# RT_SUPER_C.net
KiCad netlist of a schematic drawn in Altium Designer
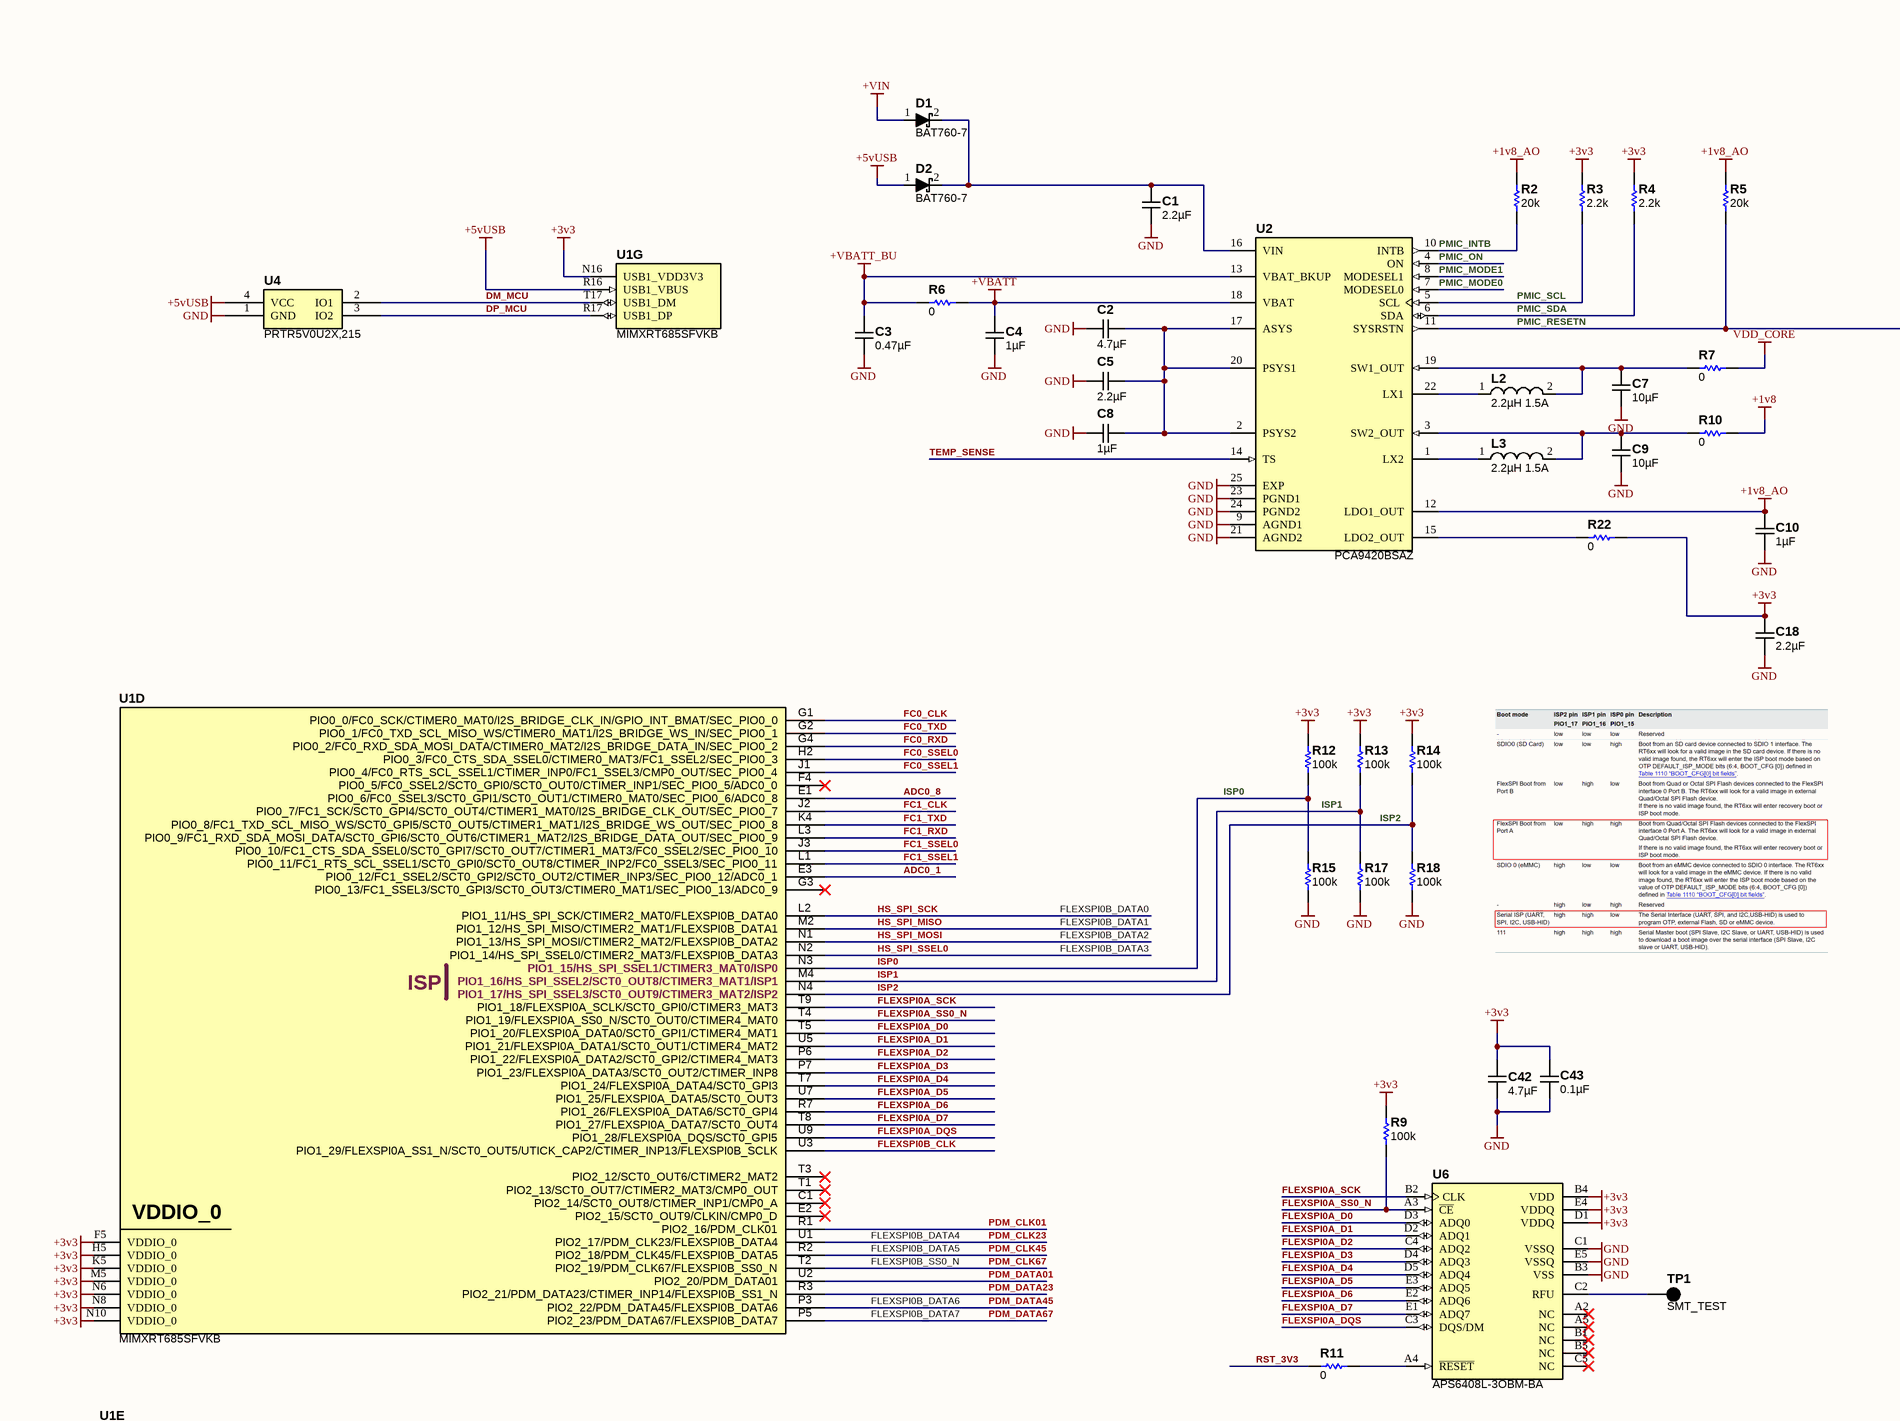
[diagram p0: RT_SUPER_C.SchDoc, top left]
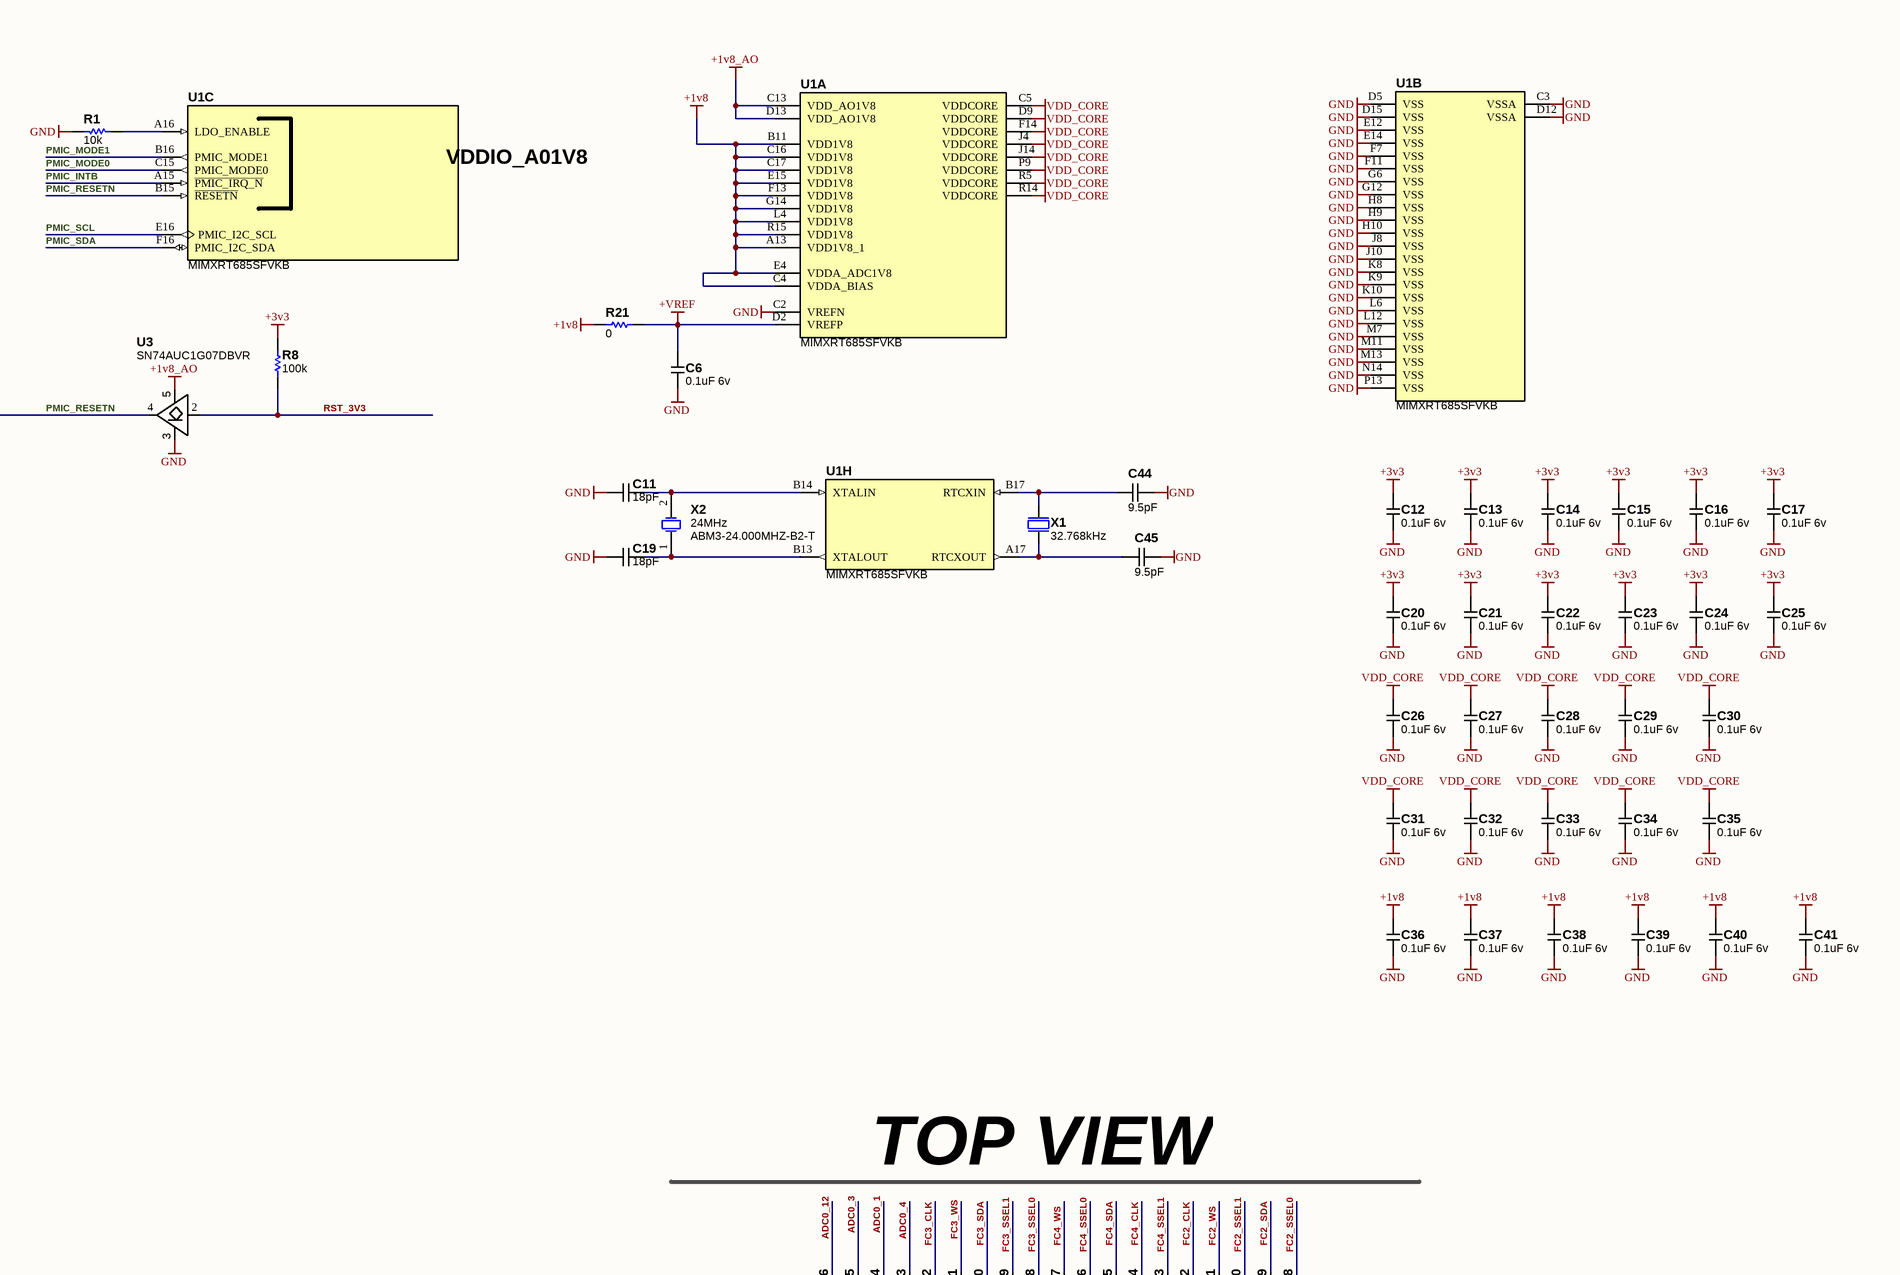
[diagram p1: RT_SUPER_C.SchDoc, top right]
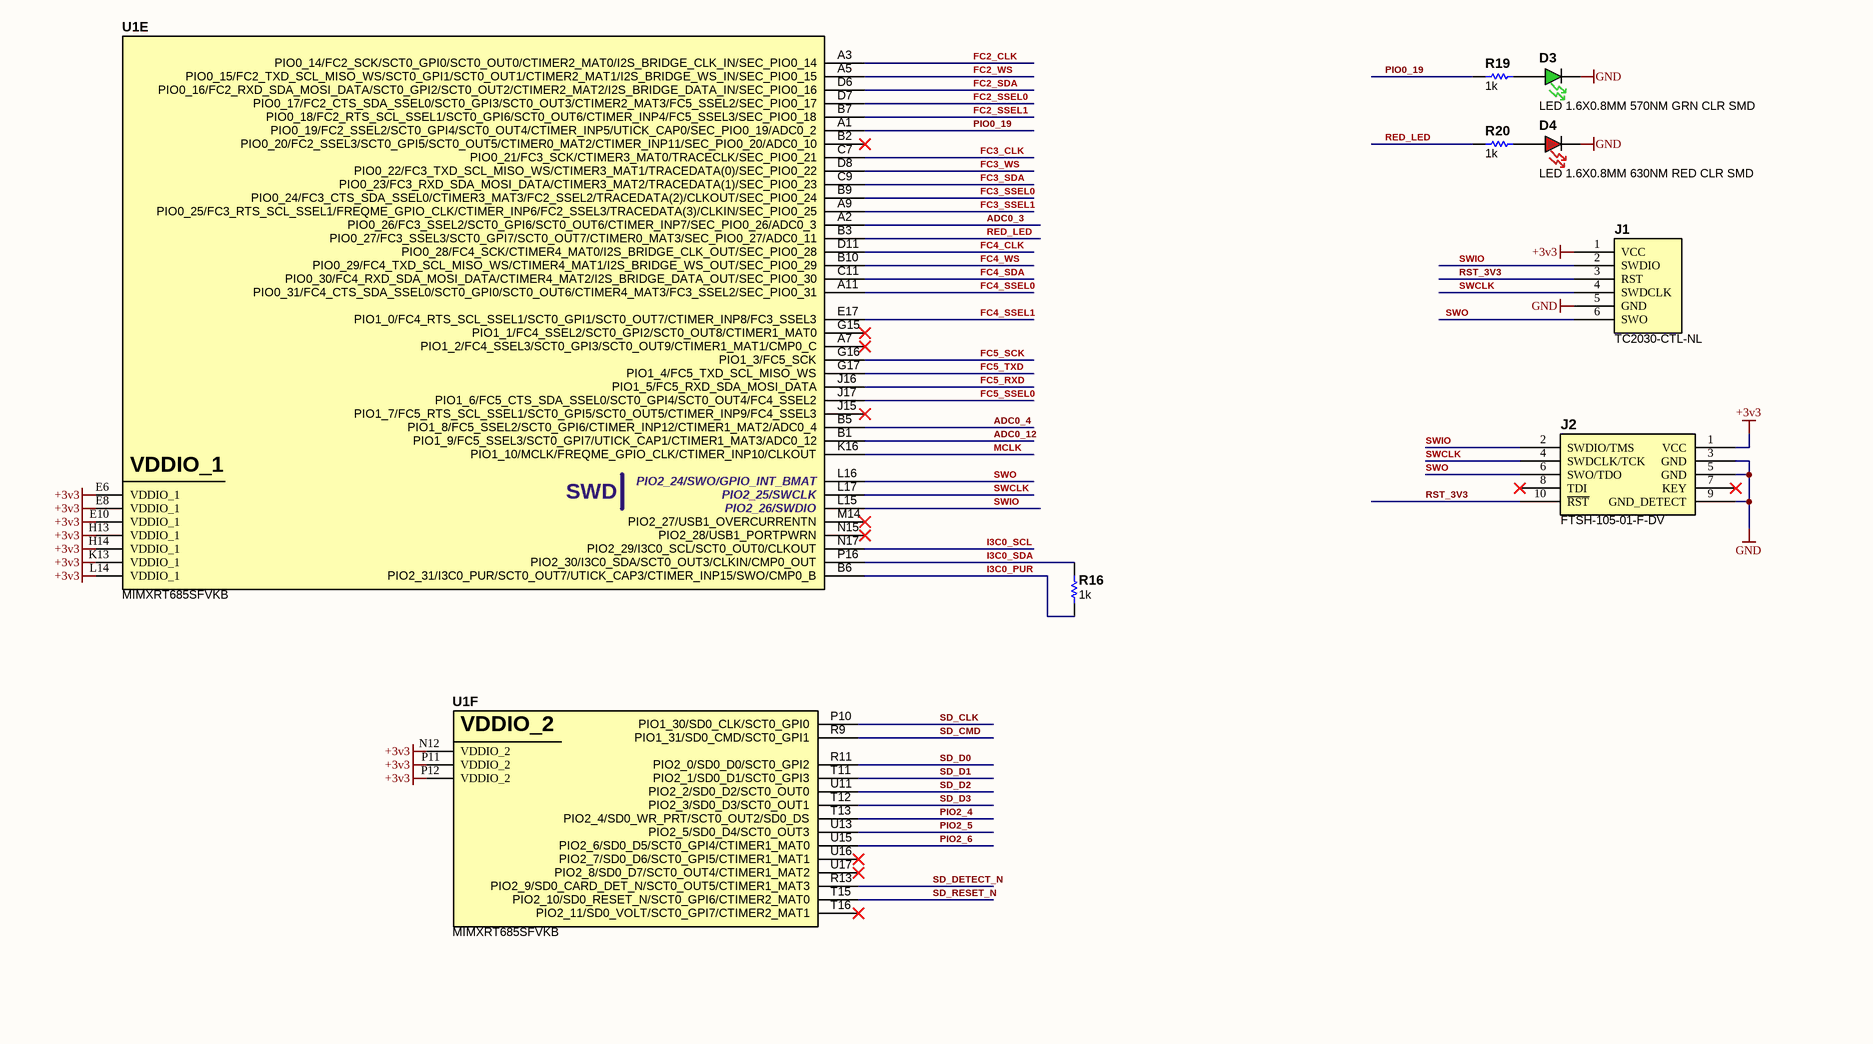
[diagram p2: RT_SUPER_C.SchDoc, bottom left]
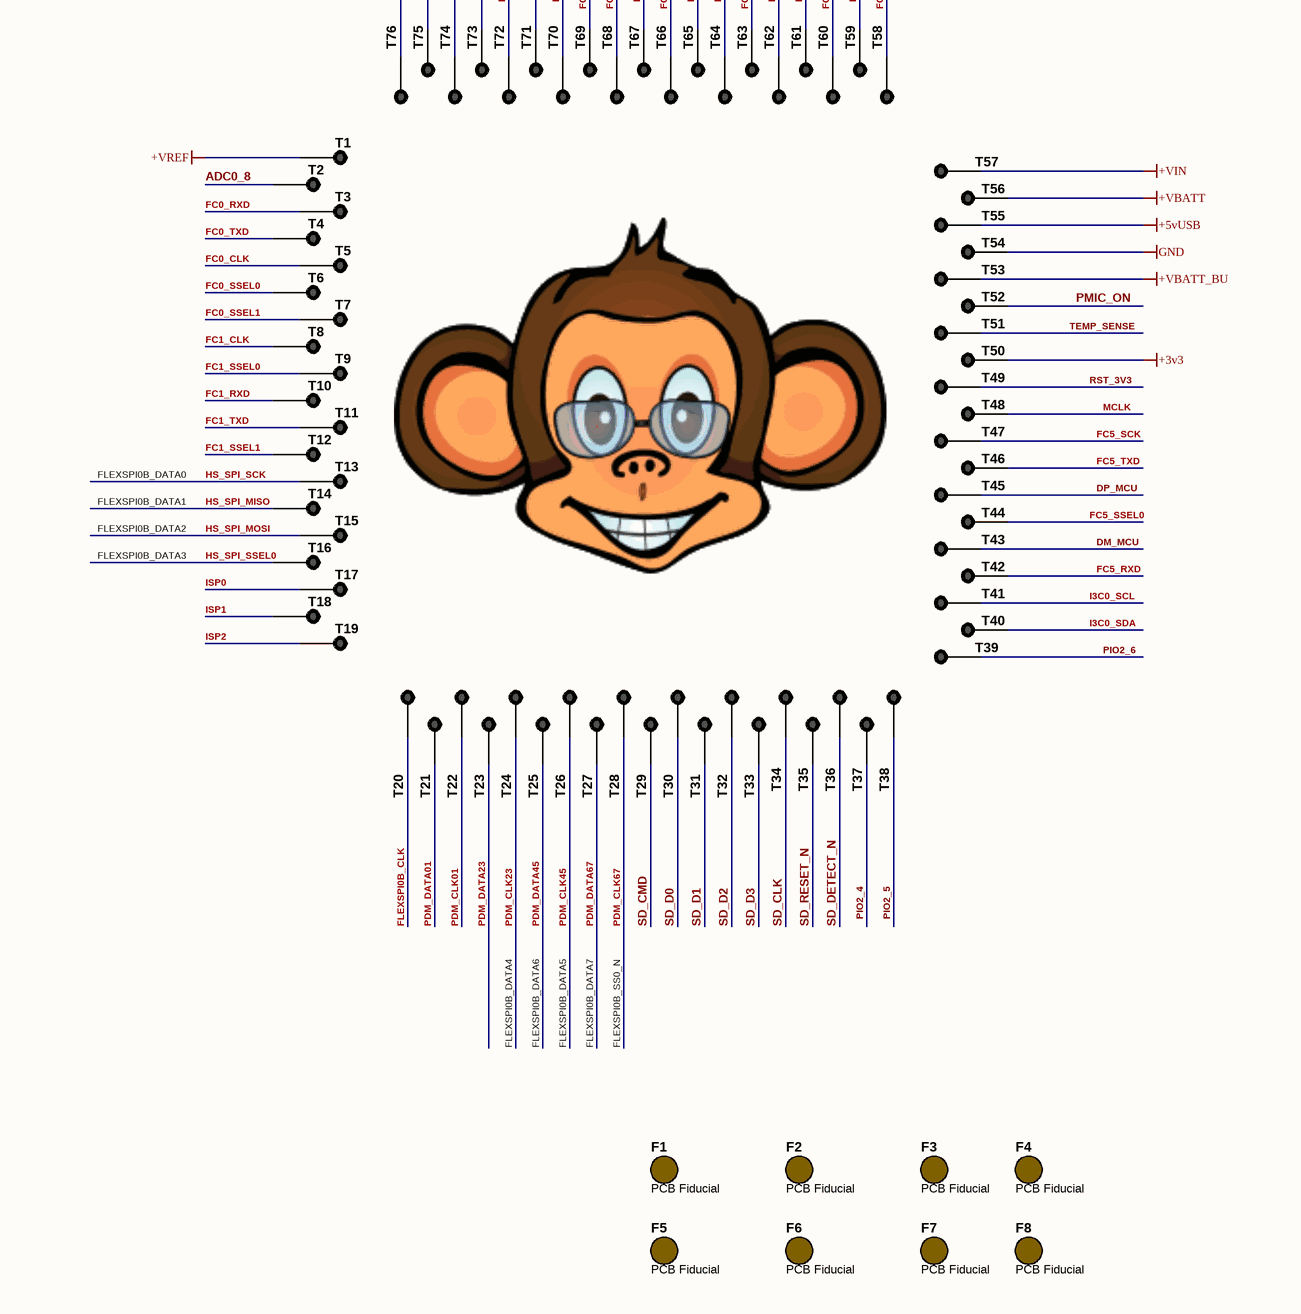
[diagram p3: RT_SUPER_C.SchDoc, bottom right]

(export (version "E")
  (design (tool "Eeschema 10.0.6"))
  (components
    (comp (ref "C1")
      (value "2.2µF")
      (footprint "C0603_0.90MM_MD")
      (description "CAP CER 2.2UF 6.3V X7R 0603")
      (fields
        (field (name "MANUFACTURER PART NUMBER") "GCM188R70J225KE22D")
        (field (name "MANUFACTURER") "Murata Electronics")
      )
      (libsource (lib "Capacitors - Murata - AEC-Q200") (part "C_2P_NP"))
    )
    (comp (ref "C2")
      (value "4.7µF")
      (footprint "C0603_1.00MM_MD")
      (description "CAP CER 4.7UF 6.3V X7S 0603")
      (fields
        (field (name "MANUFACTURER PART NUMBER") "GCJ188C70J475KE02D")
        (field (name "MANUFACTURER") "Murata Electronics")
      )
      (libsource (lib "Capacitors - Murata - AEC-Q200") (part "C_2P_NP"))
    )
    (comp (ref "C3")
      (value "0.47µF")
      (footprint "C0402_0.55MM_HD")
      (description "CAP CER 0.47UF 25V X5R 0402")
      (fields
        (field (name "MANUFACTURER PART NUMBER") "GRT155R61E474KE01D")
        (field (name "MANUFACTURER") "Murata Electronics")
      )
      (libsource (lib "Capacitors - Murata - AEC-Q200") (part "C_2P_NP"))
    )
    (comp (ref "C4")
      (value "1µF")
      (footprint "C0402_0.55MM_HD")
      (description "CAP CER 1UF 10V X7S 0402")
      (fields
        (field (name "MANUFACTURER PART NUMBER") "GCM155C71A105KE38D")
        (field (name "MANUFACTURER") "Murata Electronics")
      )
      (libsource (lib "Capacitors - Murata - AEC-Q200") (part "C_2P_NP"))
    )
    (comp (ref "C5")
      (value "2.2µF")
      (footprint "C0603_0.90MM_MD")
      (description "CAP CER 2.2UF 6.3V X7R 0603")
      (fields
        (field (name "MANUFACTURER PART NUMBER") "GCM188R70J225KE22D")
        (field (name "MANUFACTURER") "Murata Electronics")
      )
      (libsource (lib "Capacitors - Murata - AEC-Q200") (part "C_2P_NP"))
    )
    (comp (ref "C6")
      (value "0.1uF 6v")
      (footprint "C0201_PERFECT")
      (description "Cap Ceramic 0.1uF 6.3VDC X5R 10% SMD 0201 Paper T/R")
      (fields
        (field (name "MANUFACTURER PART NUMBER") "CC0201KRX5R5BB104")
        (field (name "MANUFACTURER") "Yageo")
      )
      (libsource (lib "eCapacitors") (part "CC0201KRX5R5BB104"))
    )
    (comp (ref "C7")
      (value "10µF")
      (footprint "C0603_0.90MM_MD")
      (description "CAP CER 10UF 10V X5R 0603")
      (fields
        (field (name "MANUFACTURER PART NUMBER") "GRT188R61A106ME13D")
        (field (name "MANUFACTURER") "Murata Electronics")
      )
      (libsource (lib "Capacitors - Murata - AEC-Q200") (part "C_2P_NP"))
    )
    (comp (ref "C8")
      (value "1µF")
      (footprint "C0402_0.55MM_HD")
      (description "CAP CER 1UF 10V X7S 0402")
      (fields
        (field (name "MANUFACTURER PART NUMBER") "GCM155C71A105KE38D")
        (field (name "MANUFACTURER") "Murata Electronics")
      )
      (libsource (lib "Capacitors - Murata - AEC-Q200") (part "C_2P_NP"))
    )
    (comp (ref "C9")
      (value "10µF")
      (footprint "C0603_0.90MM_MD")
      (description "CAP CER 10UF 10V X5R 0603")
      (fields
        (field (name "MANUFACTURER PART NUMBER") "GRT188R61A106ME13D")
        (field (name "MANUFACTURER") "Murata Electronics")
      )
      (libsource (lib "Capacitors - Murata - AEC-Q200") (part "C_2P_NP"))
    )
    (comp (ref "C10")
      (value "1µF")
      (footprint "C0402_0.55MM_HD")
      (description "CAP CER 1UF 10V X7S 0402")
      (fields
        (field (name "MANUFACTURER PART NUMBER") "GCM155C71A105KE38D")
        (field (name "MANUFACTURER") "Murata Electronics")
      )
      (libsource (lib "Capacitors - Murata - AEC-Q200") (part "C_2P_NP"))
    )
    (comp (ref "C11")
      (value "18pF")
      (footprint "C0402_0.55MM_HD")
      (description "CAP CER 18PF 50V C0G 0402")
      (fields
        (field (name "MANUFACTURER PART NUMBER") "CGA2B2C0G1H180J050BA")
        (field (name "MANUFACTURER") "TDK Corporation")
      )
      (libsource (lib "Capacitors - TDK- AEC-Q200") (part "C_2P_NP"))
    )
    (comp (ref "C12")
      (value "0.1uF 6v")
      (footprint "C0201_PERFECT")
      (description "Cap Ceramic 0.1uF 6.3VDC X5R 10% SMD 0201 Paper T/R")
      (fields
        (field (name "MANUFACTURER PART NUMBER") "CC0201KRX5R5BB104")
        (field (name "MANUFACTURER") "Yageo")
      )
      (libsource (lib "eCapacitors") (part "CC0201KRX5R5BB104"))
    )
    (comp (ref "C13")
      (value "0.1uF 6v")
      (footprint "C0201_PERFECT")
      (description "Cap Ceramic 0.1uF 6.3VDC X5R 10% SMD 0201 Paper T/R")
      (fields
        (field (name "MANUFACTURER PART NUMBER") "CC0201KRX5R5BB104")
        (field (name "MANUFACTURER") "Yageo")
      )
      (libsource (lib "eCapacitors") (part "CC0201KRX5R5BB104"))
    )
    (comp (ref "C14")
      (value "0.1uF 6v")
      (footprint "C0201_PERFECT")
      (description "Cap Ceramic 0.1uF 6.3VDC X5R 10% SMD 0201 Paper T/R")
      (fields
        (field (name "MANUFACTURER PART NUMBER") "CC0201KRX5R5BB104")
        (field (name "MANUFACTURER") "Yageo")
      )
      (libsource (lib "eCapacitors") (part "CC0201KRX5R5BB104"))
    )
    (comp (ref "C15")
      (value "0.1uF 6v")
      (footprint "C0201_PERFECT")
      (description "Cap Ceramic 0.1uF 6.3VDC X5R 10% SMD 0201 Paper T/R")
      (fields
        (field (name "MANUFACTURER PART NUMBER") "CC0201KRX5R5BB104")
        (field (name "MANUFACTURER") "Yageo")
      )
      (libsource (lib "eCapacitors") (part "CC0201KRX5R5BB104"))
    )
    (comp (ref "C16")
      (value "0.1uF 6v")
      (footprint "C0201_PERFECT")
      (description "Cap Ceramic 0.1uF 6.3VDC X5R 10% SMD 0201 Paper T/R")
      (fields
        (field (name "MANUFACTURER PART NUMBER") "CC0201KRX5R5BB104")
        (field (name "MANUFACTURER") "Yageo")
      )
      (libsource (lib "eCapacitors") (part "CC0201KRX5R5BB104"))
    )
    (comp (ref "C17")
      (value "0.1uF 6v")
      (footprint "C0201_PERFECT")
      (description "Cap Ceramic 0.1uF 6.3VDC X5R 10% SMD 0201 Paper T/R")
      (fields
        (field (name "MANUFACTURER PART NUMBER") "CC0201KRX5R5BB104")
        (field (name "MANUFACTURER") "Yageo")
      )
      (libsource (lib "eCapacitors") (part "CC0201KRX5R5BB104"))
    )
    (comp (ref "C18")
      (value "2.2µF")
      (footprint "C0603_0.90MM_MD")
      (description "CAP CER 2.2UF 6.3V X7R 0603")
      (fields
        (field (name "MANUFACTURER PART NUMBER") "GCM188R70J225KE22D")
        (field (name "MANUFACTURER") "Murata Electronics")
      )
      (libsource (lib "Capacitors - Murata - AEC-Q200") (part "C_2P_NP"))
    )
    (comp (ref "C19")
      (value "18pF")
      (footprint "C0402_0.55MM_HD")
      (description "CAP CER 18PF 50V C0G 0402")
      (fields
        (field (name "MANUFACTURER PART NUMBER") "CGA2B2C0G1H180J050BA")
        (field (name "MANUFACTURER") "TDK Corporation")
      )
      (libsource (lib "Capacitors - TDK- AEC-Q200") (part "C_2P_NP"))
    )
    (comp (ref "C20")
      (value "0.1uF 6v")
      (footprint "C0201_PERFECT")
      (description "Cap Ceramic 0.1uF 6.3VDC X5R 10% SMD 0201 Paper T/R")
      (fields
        (field (name "MANUFACTURER PART NUMBER") "CC0201KRX5R5BB104")
        (field (name "MANUFACTURER") "Yageo")
      )
      (libsource (lib "eCapacitors") (part "CC0201KRX5R5BB104"))
    )
    (comp (ref "C21")
      (value "0.1uF 6v")
      (footprint "C0201_PERFECT")
      (description "Cap Ceramic 0.1uF 6.3VDC X5R 10% SMD 0201 Paper T/R")
      (fields
        (field (name "MANUFACTURER PART NUMBER") "CC0201KRX5R5BB104")
        (field (name "MANUFACTURER") "Yageo")
      )
      (libsource (lib "eCapacitors") (part "CC0201KRX5R5BB104"))
    )
    (comp (ref "C22")
      (value "0.1uF 6v")
      (footprint "C0201_PERFECT")
      (description "Cap Ceramic 0.1uF 6.3VDC X5R 10% SMD 0201 Paper T/R")
      (fields
        (field (name "MANUFACTURER PART NUMBER") "CC0201KRX5R5BB104")
        (field (name "MANUFACTURER") "Yageo")
      )
      (libsource (lib "eCapacitors") (part "CC0201KRX5R5BB104"))
    )
    (comp (ref "C23")
      (value "0.1uF 6v")
      (footprint "C0201_PERFECT")
      (description "Cap Ceramic 0.1uF 6.3VDC X5R 10% SMD 0201 Paper T/R")
      (fields
        (field (name "MANUFACTURER PART NUMBER") "CC0201KRX5R5BB104")
        (field (name "MANUFACTURER") "Yageo")
      )
      (libsource (lib "eCapacitors") (part "CC0201KRX5R5BB104"))
    )
    (comp (ref "C24")
      (value "0.1uF 6v")
      (footprint "C0201_PERFECT")
      (description "Cap Ceramic 0.1uF 6.3VDC X5R 10% SMD 0201 Paper T/R")
      (fields
        (field (name "MANUFACTURER PART NUMBER") "CC0201KRX5R5BB104")
        (field (name "MANUFACTURER") "Yageo")
      )
      (libsource (lib "eCapacitors") (part "CC0201KRX5R5BB104"))
    )
    (comp (ref "C25")
      (value "0.1uF 6v")
      (footprint "C0201_PERFECT")
      (description "Cap Ceramic 0.1uF 6.3VDC X5R 10% SMD 0201 Paper T/R")
      (fields
        (field (name "MANUFACTURER PART NUMBER") "CC0201KRX5R5BB104")
        (field (name "MANUFACTURER") "Yageo")
      )
      (libsource (lib "eCapacitors") (part "CC0201KRX5R5BB104"))
    )
    (comp (ref "C26")
      (value "0.1uF 6v")
      (footprint "C0201_PERFECT")
      (description "Cap Ceramic 0.1uF 6.3VDC X5R 10% SMD 0201 Paper T/R")
      (fields
        (field (name "MANUFACTURER PART NUMBER") "CC0201KRX5R5BB104")
        (field (name "MANUFACTURER") "Yageo")
      )
      (libsource (lib "eCapacitors") (part "CC0201KRX5R5BB104"))
    )
    (comp (ref "C27")
      (value "0.1uF 6v")
      (footprint "C0201_PERFECT")
      (description "Cap Ceramic 0.1uF 6.3VDC X5R 10% SMD 0201 Paper T/R")
      (fields
        (field (name "MANUFACTURER PART NUMBER") "CC0201KRX5R5BB104")
        (field (name "MANUFACTURER") "Yageo")
      )
      (libsource (lib "eCapacitors") (part "CC0201KRX5R5BB104"))
    )
    (comp (ref "C28")
      (value "0.1uF 6v")
      (footprint "C0201_PERFECT")
      (description "Cap Ceramic 0.1uF 6.3VDC X5R 10% SMD 0201 Paper T/R")
      (fields
        (field (name "MANUFACTURER PART NUMBER") "CC0201KRX5R5BB104")
        (field (name "MANUFACTURER") "Yageo")
      )
      (libsource (lib "eCapacitors") (part "CC0201KRX5R5BB104"))
    )
    (comp (ref "C29")
      (value "0.1uF 6v")
      (footprint "C0201_PERFECT")
      (description "Cap Ceramic 0.1uF 6.3VDC X5R 10% SMD 0201 Paper T/R")
      (fields
        (field (name "MANUFACTURER PART NUMBER") "CC0201KRX5R5BB104")
        (field (name "MANUFACTURER") "Yageo")
      )
      (libsource (lib "eCapacitors") (part "CC0201KRX5R5BB104"))
    )
    (comp (ref "C30")
      (value "0.1uF 6v")
      (footprint "C0201_PERFECT")
      (description "Cap Ceramic 0.1uF 6.3VDC X5R 10% SMD 0201 Paper T/R")
      (fields
        (field (name "MANUFACTURER PART NUMBER") "CC0201KRX5R5BB104")
        (field (name "MANUFACTURER") "Yageo")
      )
      (libsource (lib "eCapacitors") (part "CC0201KRX5R5BB104"))
    )
    (comp (ref "C31")
      (value "0.1uF 6v")
      (footprint "C0201_PERFECT")
      (description "Cap Ceramic 0.1uF 6.3VDC X5R 10% SMD 0201 Paper T/R")
      (fields
        (field (name "MANUFACTURER PART NUMBER") "CC0201KRX5R5BB104")
        (field (name "MANUFACTURER") "Yageo")
      )
      (libsource (lib "eCapacitors") (part "CC0201KRX5R5BB104"))
    )
    (comp (ref "C32")
      (value "0.1uF 6v")
      (footprint "C0201_PERFECT")
      (description "Cap Ceramic 0.1uF 6.3VDC X5R 10% SMD 0201 Paper T/R")
      (fields
        (field (name "MANUFACTURER PART NUMBER") "CC0201KRX5R5BB104")
        (field (name "MANUFACTURER") "Yageo")
      )
      (libsource (lib "eCapacitors") (part "CC0201KRX5R5BB104"))
    )
    (comp (ref "C33")
      (value "0.1uF 6v")
      (footprint "C0201_PERFECT")
      (description "Cap Ceramic 0.1uF 6.3VDC X5R 10% SMD 0201 Paper T/R")
      (fields
        (field (name "MANUFACTURER PART NUMBER") "CC0201KRX5R5BB104")
        (field (name "MANUFACTURER") "Yageo")
      )
      (libsource (lib "eCapacitors") (part "CC0201KRX5R5BB104"))
    )
    (comp (ref "C34")
      (value "0.1uF 6v")
      (footprint "C0201_PERFECT")
      (description "Cap Ceramic 0.1uF 6.3VDC X5R 10% SMD 0201 Paper T/R")
      (fields
        (field (name "MANUFACTURER PART NUMBER") "CC0201KRX5R5BB104")
        (field (name "MANUFACTURER") "Yageo")
      )
      (libsource (lib "eCapacitors") (part "CC0201KRX5R5BB104"))
    )
    (comp (ref "C35")
      (value "0.1uF 6v")
      (footprint "C0201_PERFECT")
      (description "Cap Ceramic 0.1uF 6.3VDC X5R 10% SMD 0201 Paper T/R")
      (fields
        (field (name "MANUFACTURER PART NUMBER") "CC0201KRX5R5BB104")
        (field (name "MANUFACTURER") "Yageo")
      )
      (libsource (lib "eCapacitors") (part "CC0201KRX5R5BB104"))
    )
    (comp (ref "C36")
      (value "0.1uF 6v")
      (footprint "C0201_PERFECT")
      (description "Cap Ceramic 0.1uF 6.3VDC X5R 10% SMD 0201 Paper T/R")
      (fields
        (field (name "MANUFACTURER PART NUMBER") "CC0201KRX5R5BB104")
        (field (name "MANUFACTURER") "Yageo")
      )
      (libsource (lib "eCapacitors") (part "CC0201KRX5R5BB104"))
    )
    (comp (ref "C37")
      (value "0.1uF 6v")
      (footprint "C0201_PERFECT")
      (description "Cap Ceramic 0.1uF 6.3VDC X5R 10% SMD 0201 Paper T/R")
      (fields
        (field (name "MANUFACTURER PART NUMBER") "CC0201KRX5R5BB104")
        (field (name "MANUFACTURER") "Yageo")
      )
      (libsource (lib "eCapacitors") (part "CC0201KRX5R5BB104"))
    )
    (comp (ref "C38")
      (value "0.1uF 6v")
      (footprint "C0201_PERFECT")
      (description "Cap Ceramic 0.1uF 6.3VDC X5R 10% SMD 0201 Paper T/R")
      (fields
        (field (name "MANUFACTURER PART NUMBER") "CC0201KRX5R5BB104")
        (field (name "MANUFACTURER") "Yageo")
      )
      (libsource (lib "eCapacitors") (part "CC0201KRX5R5BB104"))
    )
    (comp (ref "C39")
      (value "0.1uF 6v")
      (footprint "C0201_PERFECT")
      (description "Cap Ceramic 0.1uF 6.3VDC X5R 10% SMD 0201 Paper T/R")
      (fields
        (field (name "MANUFACTURER PART NUMBER") "CC0201KRX5R5BB104")
        (field (name "MANUFACTURER") "Yageo")
      )
      (libsource (lib "eCapacitors") (part "CC0201KRX5R5BB104"))
    )
    (comp (ref "C40")
      (value "0.1uF 6v")
      (footprint "C0201_PERFECT")
      (description "Cap Ceramic 0.1uF 6.3VDC X5R 10% SMD 0201 Paper T/R")
      (fields
        (field (name "MANUFACTURER PART NUMBER") "CC0201KRX5R5BB104")
        (field (name "MANUFACTURER") "Yageo")
      )
      (libsource (lib "eCapacitors") (part "CC0201KRX5R5BB104"))
    )
    (comp (ref "C41")
      (value "0.1uF 6v")
      (footprint "C0201_PERFECT")
      (description "Cap Ceramic 0.1uF 6.3VDC X5R 10% SMD 0201 Paper T/R")
      (fields
        (field (name "MANUFACTURER PART NUMBER") "CC0201KRX5R5BB104")
        (field (name "MANUFACTURER") "Yageo")
      )
      (libsource (lib "eCapacitors") (part "CC0201KRX5R5BB104"))
    )
    (comp (ref "C42")
      (value "4.7µF")
      (footprint "C0603_1.00MM_MD")
      (description "CAP CER 4.7UF 6.3V X7S 0603")
      (fields
        (field (name "MANUFACTURER PART NUMBER") "GCJ188C70J475KE02D")
        (field (name "MANUFACTURER") "Murata Electronics")
      )
      (libsource (lib "Capacitors - Murata - AEC-Q200") (part "C_2P_NP"))
    )
    (comp (ref "C43")
      (value "0.1µF")
      (footprint "C0402_0.55MM_MD")
      (description "CAP CER 0.1UF 16V X7R 0402")
      (fields
        (field (name "MANUFACTURER PART NUMBER") "CGA2B1X7R1C104K050BC")
        (field (name "MANUFACTURER") "TDK Corporation")
      )
      (libsource (lib "Capacitors - TDK- AEC-Q200") (part "C_2P_NP"))
    )
    (comp (ref "C44")
      (value "9.5pF")
      (footprint "PERFECT_0402")
      (description "CAP CER 9.5PF 50V C0G/NP0 0402")
      (fields
        (field (name "MANUFACTURER PART NUMBER") "GCQ1555C1H9R5BB01D")
        (field (name "MANUFACTURER") "Murata Electronics")
      )
      (libsource (lib "Capacitors - Murata - AEC-Q200") (part "C_2P_NP"))
    )
    (comp (ref "C45")
      (value "9.5pF")
      (footprint "PERFECT_0402")
      (description "CAP CER 9.5PF 50V C0G/NP0 0402")
      (fields
        (field (name "MANUFACTURER PART NUMBER") "GCQ1555C1H9R5BB01D")
        (field (name "MANUFACTURER") "Murata Electronics")
      )
      (libsource (lib "Capacitors - Murata - AEC-Q200") (part "C_2P_NP"))
    )
    (comp (ref "D1")
      (value "BAT760-7")
      (footprint "D_SOD-323_P")
      (description "DIODE SCHOTTKY 30V 1A SOD323")
      (fields (field (name "MANUFACTURER") "Diodes Inc"))
      (libsource (lib "Diodes") (part "DS_1A_2C"))
    )
    (comp (ref "D2")
      (value "BAT760-7")
      (footprint "D_SOD-323_P")
      (description "DIODE SCHOTTKY 30V 1A SOD323")
      (fields (field (name "MANUFACTURER") "Diodes Inc"))
      (libsource (lib "Diodes") (part "DS_1A_2C"))
    )
    (comp (ref "D3")
      (value "LED 1.6X0.8MM 570NM GRN CLR SMD")
      (footprint "LED_0603 - GREEN")
      (fields
        (field (name "MANUFACTURER") "Kingbright Corp")
        (field (name "MANUFACTURER PART NUMBER") "APT1608CGCK")
      )
      (libsource (lib "eDiode") (part "APT1608CGCK"))
    )
    (comp (ref "D4")
      (value "LED 1.6X0.8MM 630NM RED CLR SMD")
      (footprint "LED_0603 - RED")
      (fields
        (field (name "MANUFACTURER") "Kingbright Corp")
        (field (name "MANUFACTURER PART NUMBER") "APT1608SURCK")
      )
      (libsource (lib "eDiode") (part "APT1608SURCK"))
    )
    (comp (ref "F1")
      (value "PCB Fiducial")
      (footprint "Fiducial 1mm - 2mm")
      (libsource (lib "eFiducial") (part "Fiducial"))
    )
    (comp (ref "F2")
      (value "PCB Fiducial")
      (footprint "Fiducial 1mm - 2mm")
      (libsource (lib "eFiducial") (part "Fiducial"))
    )
    (comp (ref "F3")
      (value "PCB Fiducial")
      (footprint "Fiducial 1mm - 2mm")
      (libsource (lib "eFiducial") (part "Fiducial"))
    )
    (comp (ref "F4")
      (value "PCB Fiducial")
      (footprint "Fiducial 1mm - 2mm")
      (libsource (lib "eFiducial") (part "Fiducial"))
    )
    (comp (ref "F5")
      (value "PCB Fiducial")
      (footprint "Fiducial 1mm - 2mm")
      (libsource (lib "eFiducial") (part "Fiducial"))
    )
    (comp (ref "F6")
      (value "PCB Fiducial")
      (footprint "Fiducial 1mm - 2mm")
      (libsource (lib "eFiducial") (part "Fiducial"))
    )
    (comp (ref "F7")
      (value "PCB Fiducial")
      (footprint "Fiducial 1mm - 2mm")
      (libsource (lib "eFiducial") (part "Fiducial"))
    )
    (comp (ref "F8")
      (value "PCB Fiducial")
      (footprint "Fiducial 1mm - 2mm")
      (libsource (lib "eFiducial") (part "Fiducial"))
    )
    (comp (ref "J1")
      (value "TC2030‐CTL‐NL")
      (footprint "TC2030 NO LATCH")
      (description "Tag Connect Pads - No latching Clips - ARM")
      (libsource (lib "eConnector_Debug") (part "TC2030‐CTL‐NL"))
    )
    (comp (ref "J2")
      (value "FTSH-105-01-F-DV")
      (footprint "FTSH-105-01-F-DV-K-A")
      (description "SAMTEC - FTSH-105-01-F-DV - .050 X .050")
      (fields (field (name "MANUFACTURER") "SAMTEC"))
      (libsource (lib "eConnector") (part "CORTEX-DEBUG"))
    )
    (comp (ref "L2")
      (value "2.2µH 1.5A")
      (footprint "L_NRH3012")
      (description "Inductor 2.2µH 1.5A")
      (fields
        (field (name "MANUFACTURER PART NUMBER") "NRH3012T2R2MN")
        (field (name "MANUFACTURER") "Taiyo Yuden")
      )
      (libsource (lib "Inductors") (part "L_2P"))
    )
    (comp (ref "L3")
      (value "2.2µH 1.5A")
      (footprint "L_NRH3012")
      (description "Inductor 2.2µH 1.5A")
      (fields
        (field (name "MANUFACTURER PART NUMBER") "NRH3012T2R2MN")
        (field (name "MANUFACTURER") "Taiyo Yuden")
      )
      (libsource (lib "Inductors") (part "L_2P"))
    )
    (comp (ref "R1")
      (value "10k")
      (footprint "R0402_0.40MM_HD")
      (description "RES 10K OHM 1/10W 1% 0402 SMD")
      (fields
        (field (name "MANUFACTURER PART NUMBER") "ERJ-2RKF1002X")
        (field (name "MANUFACTURER") "Panasonic Electronic Components")
      )
      (libsource (lib "Resistors - Panasonic - AEC-Q200") (part "R_2P"))
    )
    (comp (ref "R2")
      (value "20k")
      (footprint "R0402_0.40MM_HD")
      (description "RES 20K OHM 1/10W 1% 0402 SMD")
      (fields
        (field (name "MANUFACTURER PART NUMBER") "ERJ-2RKF2002X")
        (field (name "MANUFACTURER") "Panasonic Electronic Components")
      )
      (libsource (lib "Resistors - Panasonic - AEC-Q200") (part "R_2P"))
    )
    (comp (ref "R3")
      (value "2.2k")
      (footprint "R0402_0.40MM_HD")
      (description "RES 2.2K OHM 1/10W 1% 0402 SMD")
      (fields
        (field (name "MANUFACTURER PART NUMBER") "ERJ-2RKF2201X")
        (field (name "MANUFACTURER") "Panasonic Electronic Components")
      )
      (libsource (lib "Resistors - Panasonic - AEC-Q200") (part "R_2P"))
    )
    (comp (ref "R4")
      (value "2.2k")
      (footprint "R0402_0.40MM_HD")
      (description "RES 2.2K OHM 1/10W 1% 0402 SMD")
      (fields
        (field (name "MANUFACTURER PART NUMBER") "ERJ-2RKF2201X")
        (field (name "MANUFACTURER") "Panasonic Electronic Components")
      )
      (libsource (lib "Resistors - Panasonic - AEC-Q200") (part "R_2P"))
    )
    (comp (ref "R5")
      (value "20k")
      (footprint "R0402_0.40MM_HD")
      (description "RES 20K OHM 1/10W 1% 0402 SMD")
      (fields
        (field (name "MANUFACTURER PART NUMBER") "ERJ-2RKF2002X")
        (field (name "MANUFACTURER") "Panasonic Electronic Components")
      )
      (libsource (lib "Resistors - Panasonic - AEC-Q200") (part "R_2P"))
    )
    (comp (ref "R6")
      (value "0")
      (footprint "R0402_0.40MM_HD")
      (description "RES 0.0 OHM 1/10W JUMP 0402 SMD")
      (fields
        (field (name "MANUFACTURER PART NUMBER") "ERJ-2GE0R00X")
        (field (name "MANUFACTURER") "Panasonic Electronic Components")
      )
      (libsource (lib "Resistors - Panasonic - AEC-Q200") (part "R_2P"))
    )
    (comp (ref "R7")
      (value "0")
      (footprint "R0402_0.40MM_HD")
      (description "RES 0.0 OHM 1/10W JUMP 0402 SMD")
      (fields
        (field (name "MANUFACTURER PART NUMBER") "ERJ-2GE0R00X")
        (field (name "MANUFACTURER") "Panasonic Electronic Components")
      )
      (libsource (lib "Resistors - Panasonic - AEC-Q200") (part "R_2P"))
    )
    (comp (ref "R8")
      (value "100k")
      (footprint "R0402_0.40MM_HD")
      (description "RES 100K OHM 1/10W 1% 0402 SMD")
      (fields
        (field (name "MANUFACTURER PART NUMBER") "ERJ-2RKF1003X")
        (field (name "MANUFACTURER") "Panasonic Electronic Components")
      )
      (libsource (lib "Resistors - Panasonic - AEC-Q200") (part "R_2P"))
    )
    (comp (ref "R9")
      (value "100k")
      (footprint "R0402_0.40MM_HD")
      (description "RES 100K OHM 1/10W 1% 0402 SMD")
      (fields
        (field (name "MANUFACTURER PART NUMBER") "ERJ-2RKF1003X")
        (field (name "MANUFACTURER") "Panasonic Electronic Components")
      )
      (libsource (lib "Resistors - Panasonic - AEC-Q200") (part "R_2P"))
    )
    (comp (ref "R10")
      (value "0")
      (footprint "R0402_0.40MM_HD")
      (description "RES 0.0 OHM 1/10W JUMP 0402 SMD")
      (fields
        (field (name "MANUFACTURER PART NUMBER") "ERJ-2GE0R00X")
        (field (name "MANUFACTURER") "Panasonic Electronic Components")
      )
      (libsource (lib "Resistors - Panasonic - AEC-Q200") (part "R_2P"))
    )
    (comp (ref "R11")
      (value "0")
      (footprint "R0402_0.40MM_HD")
      (description "RES 0.0 OHM 1/10W JUMP 0402 SMD")
      (fields
        (field (name "MANUFACTURER PART NUMBER") "ERJ-2GE0R00X")
        (field (name "MANUFACTURER") "Panasonic Electronic Components")
      )
      (libsource (lib "Resistors - Panasonic - AEC-Q200") (part "R_2P"))
    )
    (comp (ref "R12")
      (value "100k")
      (footprint "R0402_0.40MM_HD")
      (description "RES 100K OHM 1/10W 1% 0402 SMD")
      (fields
        (field (name "MANUFACTURER PART NUMBER") "ERJ-2RKF1003X")
        (field (name "MANUFACTURER") "Panasonic Electronic Components")
      )
      (libsource (lib "Resistors - Panasonic - AEC-Q200") (part "R_2P"))
    )
    (comp (ref "R13")
      (value "100k")
      (footprint "R0402_0.40MM_HD")
      (description "RES 100K OHM 1/10W 1% 0402 SMD")
      (fields
        (field (name "MANUFACTURER PART NUMBER") "ERJ-2RKF1003X")
        (field (name "MANUFACTURER") "Panasonic Electronic Components")
      )
      (libsource (lib "Resistors - Panasonic - AEC-Q200") (part "R_2P"))
    )
    (comp (ref "R14")
      (value "100k")
      (footprint "R0402_0.40MM_HD")
      (description "RES 100K OHM 1/10W 1% 0402 SMD")
      (fields
        (field (name "MANUFACTURER PART NUMBER") "ERJ-2RKF1003X")
        (field (name "MANUFACTURER") "Panasonic Electronic Components")
      )
      (libsource (lib "Resistors - Panasonic - AEC-Q200") (part "R_2P"))
    )
    (comp (ref "R15")
      (value "100k")
      (footprint "R0402_0.40MM_HD")
      (description "RES 100K OHM 1/10W 1% 0402 SMD")
      (fields
        (field (name "MANUFACTURER PART NUMBER") "ERJ-2RKF1003X")
        (field (name "MANUFACTURER") "Panasonic Electronic Components")
      )
      (libsource (lib "Resistors - Panasonic - AEC-Q200") (part "R_2P"))
    )
    (comp (ref "R16")
      (value "1k")
      (footprint "R0402_0.40MM_HD")
      (description "RES 1K OHM 1/10W 1% 0402 SMD")
      (fields
        (field (name "MANUFACTURER PART NUMBER") "ERJ-2RKF1001X")
        (field (name "MANUFACTURER") "Panasonic Electronic Components")
      )
      (libsource (lib "Resistors - Panasonic - AEC-Q200") (part "R_2P"))
    )
    (comp (ref "R17")
      (value "100k")
      (footprint "R0402_0.40MM_HD")
      (description "RES 100K OHM 1/10W 1% 0402 SMD")
      (fields
        (field (name "MANUFACTURER PART NUMBER") "ERJ-2RKF1003X")
        (field (name "MANUFACTURER") "Panasonic Electronic Components")
      )
      (libsource (lib "Resistors - Panasonic - AEC-Q200") (part "R_2P"))
    )
    (comp (ref "R18")
      (value "100k")
      (footprint "R0402_0.40MM_HD")
      (description "RES 100K OHM 1/10W 1% 0402 SMD")
      (fields
        (field (name "MANUFACTURER PART NUMBER") "ERJ-2RKF1003X")
        (field (name "MANUFACTURER") "Panasonic Electronic Components")
      )
      (libsource (lib "Resistors - Panasonic - AEC-Q200") (part "R_2P"))
    )
    (comp (ref "R19")
      (value "1k")
      (footprint "R0402_0.40MM_HD")
      (description "RES 1K OHM 1/10W 1% 0402 SMD")
      (fields
        (field (name "MANUFACTURER PART NUMBER") "ERJ-2RKF1001X")
        (field (name "MANUFACTURER") "Panasonic Electronic Components")
      )
      (libsource (lib "Resistors - Panasonic - AEC-Q200") (part "R_2P"))
    )
    (comp (ref "R20")
      (value "1k")
      (footprint "R0402_0.40MM_HD")
      (description "RES 1K OHM 1/10W 1% 0402 SMD")
      (fields
        (field (name "MANUFACTURER PART NUMBER") "ERJ-2RKF1001X")
        (field (name "MANUFACTURER") "Panasonic Electronic Components")
      )
      (libsource (lib "Resistors - Panasonic - AEC-Q200") (part "R_2P"))
    )
    (comp (ref "R21")
      (value "0")
      (footprint "R0402_0.40MM_HD")
      (description "RES 0.0 OHM 1/10W JUMP 0402 SMD")
      (fields
        (field (name "MANUFACTURER PART NUMBER") "ERJ-2GE0R00X")
        (field (name "MANUFACTURER") "Panasonic Electronic Components")
      )
      (libsource (lib "Resistors - Panasonic - AEC-Q200") (part "R_2P"))
    )
    (comp (ref "R22")
      (value "0")
      (footprint "R0402_0.40MM_HD")
      (description "RES 0.0 OHM 1/10W JUMP 0402 SMD")
      (fields
        (field (name "MANUFACTURER PART NUMBER") "ERJ-2GE0R00X")
        (field (name "MANUFACTURER") "Panasonic Electronic Components")
      )
      (libsource (lib "Resistors - Panasonic - AEC-Q200") (part "R_2P"))
    )
    (comp (ref "T1")
      (value "SOLDER_HOLE")
      (footprint "MACHINE_PIN_SOLDERHOLE")
      (libsource (lib "eConnector") (part "SOLDER_HOLE"))
    )
    (comp (ref "T2")
      (value "SOLDER_HOLE")
      (footprint "MACHINE_PIN_SOLDERHOLE")
      (libsource (lib "eConnector") (part "SOLDER_HOLE"))
    )
    (comp (ref "T3")
      (value "SOLDER_HOLE")
      (footprint "MACHINE_PIN_SOLDERHOLE")
      (libsource (lib "eConnector") (part "SOLDER_HOLE"))
    )
    (comp (ref "T4")
      (value "SOLDER_HOLE")
      (footprint "MACHINE_PIN_SOLDERHOLE")
      (libsource (lib "eConnector") (part "SOLDER_HOLE"))
    )
    (comp (ref "T5")
      (value "SOLDER_HOLE")
      (footprint "MACHINE_PIN_SOLDERHOLE")
      (libsource (lib "eConnector") (part "SOLDER_HOLE"))
    )
    (comp (ref "T6")
      (value "SOLDER_HOLE")
      (footprint "MACHINE_PIN_SOLDERHOLE")
      (libsource (lib "eConnector") (part "SOLDER_HOLE"))
    )
    (comp (ref "T7")
      (value "SOLDER_HOLE")
      (footprint "MACHINE_PIN_SOLDERHOLE")
      (libsource (lib "eConnector") (part "SOLDER_HOLE"))
    )
    (comp (ref "T8")
      (value "SOLDER_HOLE")
      (footprint "MACHINE_PIN_SOLDERHOLE")
      (libsource (lib "eConnector") (part "SOLDER_HOLE"))
    )
    (comp (ref "T9")
      (value "SOLDER_HOLE")
      (footprint "MACHINE_PIN_SOLDERHOLE")
      (libsource (lib "eConnector") (part "SOLDER_HOLE"))
    )
    (comp (ref "T10")
      (value "SOLDER_HOLE")
      (footprint "MACHINE_PIN_SOLDERHOLE")
      (libsource (lib "eConnector") (part "SOLDER_HOLE"))
    )
    (comp (ref "T11")
      (value "SOLDER_HOLE")
      (footprint "MACHINE_PIN_SOLDERHOLE")
      (libsource (lib "eConnector") (part "SOLDER_HOLE"))
    )
    (comp (ref "T12")
      (value "SOLDER_HOLE")
      (footprint "MACHINE_PIN_SOLDERHOLE")
      (libsource (lib "eConnector") (part "SOLDER_HOLE"))
    )
    (comp (ref "T13")
      (value "SOLDER_HOLE")
      (footprint "MACHINE_PIN_SOLDERHOLE")
      (libsource (lib "eConnector") (part "SOLDER_HOLE"))
    )
    (comp (ref "T14")
      (value "SOLDER_HOLE")
      (footprint "MACHINE_PIN_SOLDERHOLE")
      (libsource (lib "eConnector") (part "SOLDER_HOLE"))
    )
    (comp (ref "T15")
      (value "SOLDER_HOLE")
      (footprint "MACHINE_PIN_SOLDERHOLE")
      (libsource (lib "eConnector") (part "SOLDER_HOLE"))
    )
    (comp (ref "T16")
      (value "SOLDER_HOLE")
      (footprint "MACHINE_PIN_SOLDERHOLE")
      (libsource (lib "eConnector") (part "SOLDER_HOLE"))
    )
    (comp (ref "T17")
      (value "SOLDER_HOLE")
      (footprint "MACHINE_PIN_SOLDERHOLE")
      (libsource (lib "eConnector") (part "SOLDER_HOLE"))
    )
    (comp (ref "T18")
      (value "SOLDER_HOLE")
      (footprint "MACHINE_PIN_SOLDERHOLE")
      (libsource (lib "eConnector") (part "SOLDER_HOLE"))
    )
    (comp (ref "T19")
      (value "SOLDER_HOLE")
      (footprint "MACHINE_PIN_SOLDERHOLE")
      (libsource (lib "eConnector") (part "SOLDER_HOLE"))
    )
    (comp (ref "T20")
      (value "SOLDER_HOLE")
      (footprint "MACHINE_PIN_SOLDERHOLE")
      (libsource (lib "eConnector") (part "SOLDER_HOLE"))
    )
    (comp (ref "T21")
      (value "SOLDER_HOLE")
      (footprint "MACHINE_PIN_SOLDERHOLE")
      (libsource (lib "eConnector") (part "SOLDER_HOLE"))
    )
    (comp (ref "T22")
      (value "SOLDER_HOLE")
      (footprint "MACHINE_PIN_SOLDERHOLE")
      (libsource (lib "eConnector") (part "SOLDER_HOLE"))
    )
    (comp (ref "T23")
      (value "SOLDER_HOLE")
      (footprint "MACHINE_PIN_SOLDERHOLE")
      (libsource (lib "eConnector") (part "SOLDER_HOLE"))
    )
    (comp (ref "T24")
      (value "SOLDER_HOLE")
      (footprint "MACHINE_PIN_SOLDERHOLE")
      (libsource (lib "eConnector") (part "SOLDER_HOLE"))
    )
    (comp (ref "T25")
      (value "SOLDER_HOLE")
      (footprint "MACHINE_PIN_SOLDERHOLE")
      (libsource (lib "eConnector") (part "SOLDER_HOLE"))
    )
    (comp (ref "T26")
      (value "SOLDER_HOLE")
      (footprint "MACHINE_PIN_SOLDERHOLE")
      (libsource (lib "eConnector") (part "SOLDER_HOLE"))
    )
    (comp (ref "T27")
      (value "SOLDER_HOLE")
      (footprint "MACHINE_PIN_SOLDERHOLE")
      (libsource (lib "eConnector") (part "SOLDER_HOLE"))
    )
    (comp (ref "T28")
      (value "SOLDER_HOLE")
      (footprint "MACHINE_PIN_SOLDERHOLE")
      (libsource (lib "eConnector") (part "SOLDER_HOLE"))
    )
    (comp (ref "T29")
      (value "SOLDER_HOLE")
      (footprint "MACHINE_PIN_SOLDERHOLE")
      (libsource (lib "eConnector") (part "SOLDER_HOLE"))
    )
    (comp (ref "T30")
      (value "SOLDER_HOLE")
      (footprint "MACHINE_PIN_SOLDERHOLE")
      (libsource (lib "eConnector") (part "SOLDER_HOLE"))
    )
    (comp (ref "T31")
      (value "SOLDER_HOLE")
      (footprint "MACHINE_PIN_SOLDERHOLE")
      (libsource (lib "eConnector") (part "SOLDER_HOLE"))
    )
    (comp (ref "T32")
      (value "SOLDER_HOLE")
      (footprint "MACHINE_PIN_SOLDERHOLE")
      (libsource (lib "eConnector") (part "SOLDER_HOLE"))
    )
    (comp (ref "T33")
      (value "SOLDER_HOLE")
      (footprint "MACHINE_PIN_SOLDERHOLE")
      (libsource (lib "eConnector") (part "SOLDER_HOLE"))
    )
    (comp (ref "T34")
      (value "SOLDER_HOLE")
      (footprint "MACHINE_PIN_SOLDERHOLE")
      (libsource (lib "eConnector") (part "SOLDER_HOLE"))
    )
    (comp (ref "T35")
      (value "SOLDER_HOLE")
      (footprint "MACHINE_PIN_SOLDERHOLE")
      (libsource (lib "eConnector") (part "SOLDER_HOLE"))
    )
    (comp (ref "T36")
      (value "SOLDER_HOLE")
      (footprint "MACHINE_PIN_SOLDERHOLE")
      (libsource (lib "eConnector") (part "SOLDER_HOLE"))
    )
    (comp (ref "T37")
      (value "SOLDER_HOLE")
      (footprint "MACHINE_PIN_SOLDERHOLE")
      (libsource (lib "eConnector") (part "SOLDER_HOLE"))
    )
    (comp (ref "T38")
      (value "SOLDER_HOLE")
      (footprint "MACHINE_PIN_SOLDERHOLE")
      (libsource (lib "eConnector") (part "SOLDER_HOLE"))
    )
    (comp (ref "T39")
      (value "SOLDER_HOLE")
      (footprint "MACHINE_PIN_SOLDERHOLE")
      (libsource (lib "eConnector") (part "SOLDER_HOLE"))
    )
    (comp (ref "T40")
      (value "SOLDER_HOLE")
      (footprint "MACHINE_PIN_SOLDERHOLE")
      (libsource (lib "eConnector") (part "SOLDER_HOLE"))
    )
    (comp (ref "T41")
      (value "SOLDER_HOLE")
      (footprint "MACHINE_PIN_SOLDERHOLE")
      (libsource (lib "eConnector") (part "SOLDER_HOLE"))
    )
    (comp (ref "T42")
      (value "SOLDER_HOLE")
      (footprint "MACHINE_PIN_SOLDERHOLE")
      (libsource (lib "eConnector") (part "SOLDER_HOLE"))
    )
    (comp (ref "T43")
      (value "SOLDER_HOLE")
      (footprint "MACHINE_PIN_SOLDERHOLE")
      (libsource (lib "eConnector") (part "SOLDER_HOLE"))
    )
    (comp (ref "T44")
      (value "SOLDER_HOLE")
      (footprint "MACHINE_PIN_SOLDERHOLE")
      (libsource (lib "eConnector") (part "SOLDER_HOLE"))
    )
    (comp (ref "T45")
      (value "SOLDER_HOLE")
      (footprint "MACHINE_PIN_SOLDERHOLE")
      (libsource (lib "eConnector") (part "SOLDER_HOLE"))
    )
    (comp (ref "T46")
      (value "SOLDER_HOLE")
      (footprint "MACHINE_PIN_SOLDERHOLE")
      (libsource (lib "eConnector") (part "SOLDER_HOLE"))
    )
    (comp (ref "T47")
      (value "SOLDER_HOLE")
      (footprint "MACHINE_PIN_SOLDERHOLE")
      (libsource (lib "eConnector") (part "SOLDER_HOLE"))
    )
    (comp (ref "T48")
      (value "SOLDER_HOLE")
      (footprint "MACHINE_PIN_SOLDERHOLE")
      (libsource (lib "eConnector") (part "SOLDER_HOLE"))
    )
    (comp (ref "T49")
      (value "SOLDER_HOLE")
      (footprint "MACHINE_PIN_SOLDERHOLE")
      (libsource (lib "eConnector") (part "SOLDER_HOLE"))
    )
    (comp (ref "T50")
      (value "SOLDER_HOLE")
      (footprint "MACHINE_PIN_SOLDERHOLE")
      (libsource (lib "eConnector") (part "SOLDER_HOLE"))
    )
    (comp (ref "T51")
      (value "SOLDER_HOLE")
      (footprint "MACHINE_PIN_SOLDERHOLE")
      (libsource (lib "eConnector") (part "SOLDER_HOLE"))
    )
    (comp (ref "T52")
      (value "SOLDER_HOLE")
      (footprint "MACHINE_PIN_SOLDERHOLE")
      (libsource (lib "eConnector") (part "SOLDER_HOLE"))
    )
    (comp (ref "T53")
      (value "SOLDER_HOLE")
      (footprint "MACHINE_PIN_SOLDERHOLE")
      (libsource (lib "eConnector") (part "SOLDER_HOLE"))
    )
    (comp (ref "T54")
      (value "SOLDER_HOLE")
      (footprint "MACHINE_PIN_SOLDERHOLE")
      (libsource (lib "eConnector") (part "SOLDER_HOLE"))
    )
    (comp (ref "T55")
      (value "SOLDER_HOLE")
      (footprint "MACHINE_PIN_SOLDERHOLE")
      (libsource (lib "eConnector") (part "SOLDER_HOLE"))
    )
    (comp (ref "T56")
      (value "SOLDER_HOLE")
      (footprint "MACHINE_PIN_SOLDERHOLE")
      (libsource (lib "eConnector") (part "SOLDER_HOLE"))
    )
    (comp (ref "T57")
      (value "SOLDER_HOLE")
      (footprint "MACHINE_PIN_SOLDERHOLE")
      (libsource (lib "eConnector") (part "SOLDER_HOLE"))
    )
    (comp (ref "T58")
      (value "SOLDER_HOLE")
      (footprint "MACHINE_PIN_SOLDERHOLE")
      (libsource (lib "eConnector") (part "SOLDER_HOLE"))
    )
    (comp (ref "T59")
      (value "SOLDER_HOLE")
      (footprint "MACHINE_PIN_SOLDERHOLE")
      (libsource (lib "eConnector") (part "SOLDER_HOLE"))
    )
    (comp (ref "T60")
      (value "SOLDER_HOLE")
      (footprint "MACHINE_PIN_SOLDERHOLE")
      (libsource (lib "eConnector") (part "SOLDER_HOLE"))
    )
    (comp (ref "T61")
      (value "SOLDER_HOLE")
      (footprint "MACHINE_PIN_SOLDERHOLE")
      (libsource (lib "eConnector") (part "SOLDER_HOLE"))
    )
    (comp (ref "T62")
      (value "SOLDER_HOLE")
      (footprint "MACHINE_PIN_SOLDERHOLE")
      (libsource (lib "eConnector") (part "SOLDER_HOLE"))
    )
    (comp (ref "T63")
      (value "SOLDER_HOLE")
      (footprint "MACHINE_PIN_SOLDERHOLE")
      (libsource (lib "eConnector") (part "SOLDER_HOLE"))
    )
    (comp (ref "T64")
      (value "SOLDER_HOLE")
      (footprint "MACHINE_PIN_SOLDERHOLE")
      (libsource (lib "eConnector") (part "SOLDER_HOLE"))
    )
    (comp (ref "T65")
      (value "SOLDER_HOLE")
      (footprint "MACHINE_PIN_SOLDERHOLE")
      (libsource (lib "eConnector") (part "SOLDER_HOLE"))
    )
    (comp (ref "T66")
      (value "SOLDER_HOLE")
      (footprint "MACHINE_PIN_SOLDERHOLE")
      (libsource (lib "eConnector") (part "SOLDER_HOLE"))
    )
    (comp (ref "T67")
      (value "SOLDER_HOLE")
      (footprint "MACHINE_PIN_SOLDERHOLE")
      (libsource (lib "eConnector") (part "SOLDER_HOLE"))
    )
    (comp (ref "T68")
      (value "SOLDER_HOLE")
      (footprint "MACHINE_PIN_SOLDERHOLE")
      (libsource (lib "eConnector") (part "SOLDER_HOLE"))
    )
    (comp (ref "T69")
      (value "SOLDER_HOLE")
      (footprint "MACHINE_PIN_SOLDERHOLE")
      (libsource (lib "eConnector") (part "SOLDER_HOLE"))
    )
    (comp (ref "T70")
      (value "SOLDER_HOLE")
      (footprint "MACHINE_PIN_SOLDERHOLE")
      (libsource (lib "eConnector") (part "SOLDER_HOLE"))
    )
    (comp (ref "T71")
      (value "SOLDER_HOLE")
      (footprint "MACHINE_PIN_SOLDERHOLE")
      (libsource (lib "eConnector") (part "SOLDER_HOLE"))
    )
    (comp (ref "T72")
      (value "SOLDER_HOLE")
      (footprint "MACHINE_PIN_SOLDERHOLE")
      (libsource (lib "eConnector") (part "SOLDER_HOLE"))
    )
    (comp (ref "T73")
      (value "SOLDER_HOLE")
      (footprint "MACHINE_PIN_SOLDERHOLE")
      (libsource (lib "eConnector") (part "SOLDER_HOLE"))
    )
    (comp (ref "T74")
      (value "SOLDER_HOLE")
      (footprint "MACHINE_PIN_SOLDERHOLE")
      (libsource (lib "eConnector") (part "SOLDER_HOLE"))
    )
    (comp (ref "T75")
      (value "SOLDER_HOLE")
      (footprint "MACHINE_PIN_SOLDERHOLE")
      (libsource (lib "eConnector") (part "SOLDER_HOLE"))
    )
    (comp (ref "T76")
      (value "SOLDER_HOLE")
      (footprint "MACHINE_PIN_SOLDERHOLE")
      (libsource (lib "eConnector") (part "SOLDER_HOLE"))
    )
    (comp (ref "TP1")
      (value "SMT_TEST")
      (footprint "SMT_TP - 20")
      (libsource (lib "eTestPoint") (part "SMT_TEST"))
    )
    (comp (ref "U1")
      (value "MIMXRT685SFVKB")
      (footprint "VFBGA176")
      (description "SOC i.MX ARM Cortex M33 176-Pin VFBGA Tray")
      (fields (field (name "MANUFACTURER") "NXP Semiconductors"))
      (libsource (lib "eIC") (part "MIMXRT685SFVKB"))
    )
    (comp (ref "U2")
      (value "PCA9420BSAZ")
      (footprint "PCA9420")
      (description "Power Management IC for Low-Power Microcontroller Applications 24-Pin HVQFN")
      (fields (field (name "MANUFACTURER") "NXP Semiconductors"))
      (libsource (lib "eIC") (part "PCA9420BSAZ"))
    )
    (comp (ref "U3")
      (value "SN74AUC1G07DBVR")
      (footprint "SOT23-5")
      (description "IC BUFF NON-INVERT 2.7 V SOT23-5")
      (fields (field (name "MANUFACTURER") "Texas Instruments"))
      (libsource (lib "eIC") (part "SN74AUC1G07DBVR"))
    )
    (comp (ref "U4")
      (value "PRTR5V0U2X,215")
      (footprint "SOT143B")
      (description "TVS DIODE 5.5VWM SOT143B")
      (fields (field (name "MANUFACTURER") "NXP Semiconductors"))
      (libsource (lib "eDiode") (part "PRTR5V0U2X,215"))
    )
    (comp (ref "U6")
      (value "APS6408L-3OBM-BA")
      (footprint "BGA24C100P5X5_600X800X120")
      (description "3.3v Double-Data-Rate Octal SPI Xccela PSRAM")
      (fields (field (name "MANUFACTURER") "AP Memory"))
      (libsource (lib "eIC") (part "APS6408L-3OBM-BA"))
    )
    (comp (ref "X1")
      (value "32.768kHz")
      (footprint "XTAL_3215")
      (description "CRYSTAL 32.768KHZ 9PF SMD")
      (fields
        (field (name "MANUFACTURER") "NDK")
        (field (name "MANUFACTURER PART NUMBER") "NX3215SA-32.768K-STD-MUA-9")
      )
      (libsource (lib "eCrystal") (part "NX3215SA-32.768K-STD-MUA-9"))
    )
    (comp (ref "X2")
      (value "24MHz")
      (footprint "ABM3")
      (description "CRYSTAL 24.000MHZ 18PF SMD")
      (fields
        (field (name "MANUFACTURER") "Abracon Corporation")
        (field (name "MANUFACTURER PART NUMBER") "ABM3-24.000MHZ-B2-T")
      )
      (libsource (lib "eCrystal") (part "ABM3-24.000MHZ-B2-T"))
    )
  )
  (nets
    (net (code "1") (name "+1v8") (class "Default")
      (node (ref "C36") (pin "2") (pinfunction "2_2") (pintype "passive"))
      (node (ref "C37") (pin "2") (pinfunction "2_2") (pintype "passive"))
      (node (ref "C38") (pin "2") (pinfunction "2_2") (pintype "passive"))
      (node (ref "C39") (pin "2") (pinfunction "2_2") (pintype "passive"))
      (node (ref "C40") (pin "2") (pinfunction "2_2") (pintype "passive"))
      (node (ref "C41") (pin "2") (pinfunction "2_2") (pintype "passive"))
      (node (ref "R10") (pin "2") (pinfunction "2_2") (pintype "passive"))
      (node (ref "R21") (pin "1") (pinfunction "1_1") (pintype "passive"))
      (node (ref "U1") (pin "A13") (pinfunction "VDD1V8_1_A13") (pintype "power_in"))
      (node (ref "U1") (pin "B11") (pinfunction "VDD1V8_B11") (pintype "power_in"))
      (node (ref "U1") (pin "C16") (pinfunction "VDD1V8_C16") (pintype "power_in"))
      (node (ref "U1") (pin "C17") (pinfunction "VDD1V8_C17") (pintype "power_in"))
      (node (ref "U1") (pin "C4") (pinfunction "VDDA_BIAS_C4") (pintype "power_in"))
      (node (ref "U1") (pin "E15") (pinfunction "VDD1V8_E15") (pintype "power_in"))
      (node (ref "U1") (pin "E4") (pinfunction "VDDA_ADC1V8_E4") (pintype "power_in"))
      (node (ref "U1") (pin "F13") (pinfunction "VDD1V8_F13") (pintype "power_in"))
      (node (ref "U1") (pin "G14") (pinfunction "VDD1V8_G14") (pintype "power_in"))
      (node (ref "U1") (pin "L4") (pinfunction "VDD1V8_L4") (pintype "power_in"))
      (node (ref "U1") (pin "R15") (pinfunction "VDD1V8_R15") (pintype "power_in"))
    )
    (net (code "2") (name "+1v8_AO") (class "Default")
      (node (ref "C10") (pin "2") (pinfunction "1_2") (pintype "passive"))
      (node (ref "R2") (pin "2") (pinfunction "2_2") (pintype "passive"))
      (node (ref "R5") (pin "2") (pinfunction "2_2") (pintype "passive"))
      (node (ref "U1") (pin "C13") (pinfunction "VDD_AO1V8_C13") (pintype "power_in"))
      (node (ref "U1") (pin "D13") (pinfunction "VDD_AO1V8_D13") (pintype "power_in"))
      (node (ref "U2") (pin "12") (pinfunction "LDO1_OUT_12") (pintype "power_in"))
      (node (ref "U3") (pin "5") (pinfunction "VCC_5") (pintype "passive"))
    )
    (net (code "3") (name "+3v3") (class "Default")
      (node (ref "C12") (pin "2") (pinfunction "2_2") (pintype "passive"))
      (node (ref "C13") (pin "2") (pinfunction "2_2") (pintype "passive"))
      (node (ref "C14") (pin "2") (pinfunction "2_2") (pintype "passive"))
      (node (ref "C15") (pin "2") (pinfunction "2_2") (pintype "passive"))
      (node (ref "C16") (pin "2") (pinfunction "2_2") (pintype "passive"))
      (node (ref "C17") (pin "2") (pinfunction "2_2") (pintype "passive"))
      (node (ref "C18") (pin "2") (pinfunction "1_2") (pintype "passive"))
      (node (ref "C20") (pin "2") (pinfunction "2_2") (pintype "passive"))
      (node (ref "C21") (pin "2") (pinfunction "2_2") (pintype "passive"))
      (node (ref "C22") (pin "2") (pinfunction "2_2") (pintype "passive"))
      (node (ref "C23") (pin "2") (pinfunction "2_2") (pintype "passive"))
      (node (ref "C24") (pin "2") (pinfunction "2_2") (pintype "passive"))
      (node (ref "C25") (pin "2") (pinfunction "2_2") (pintype "passive"))
      (node (ref "C42") (pin "1") (pinfunction "1_1") (pintype "passive"))
      (node (ref "C43") (pin "1") (pinfunction "1_1") (pintype "passive"))
      (node (ref "J1") (pin "1") (pinfunction "VCC_1") (pintype "passive"))
      (node (ref "J2") (pin "1") (pinfunction "VCC_1") (pintype "passive"))
      (node (ref "R12") (pin "2") (pinfunction "2_2") (pintype "passive"))
      (node (ref "R13") (pin "2") (pinfunction "2_2") (pintype "passive"))
      (node (ref "R14") (pin "2") (pinfunction "2_2") (pintype "passive"))
      (node (ref "R22") (pin "2") (pinfunction "2_2") (pintype "passive"))
      (node (ref "R3") (pin "2") (pinfunction "2_2") (pintype "passive"))
      (node (ref "R4") (pin "2") (pinfunction "2_2") (pintype "passive"))
      (node (ref "R8") (pin "2") (pinfunction "2_2") (pintype "passive"))
      (node (ref "R9") (pin "2") (pinfunction "2_2") (pintype "passive"))
      (node (ref "T50") (pin "1") (pinfunction "1_1") (pintype "passive"))
      (node (ref "U1") (pin "E10") (pinfunction "VDDIO_1_E10") (pintype "power_in"))
      (node (ref "U1") (pin "E6") (pinfunction "VDDIO_1_E6") (pintype "power_in"))
      (node (ref "U1") (pin "E8") (pinfunction "VDDIO_1_E8") (pintype "power_in"))
      (node (ref "U1") (pin "F5") (pinfunction "VDDIO_0_F5") (pintype "power_in"))
      (node (ref "U1") (pin "H13") (pinfunction "VDDIO_1_H13") (pintype "power_in"))
      (node (ref "U1") (pin "H14") (pinfunction "VDDIO_1_H14") (pintype "power_in"))
      (node (ref "U1") (pin "H5") (pinfunction "VDDIO_0_H5") (pintype "power_in"))
      (node (ref "U1") (pin "K13") (pinfunction "VDDIO_1_K13") (pintype "power_in"))
      (node (ref "U1") (pin "K5") (pinfunction "VDDIO_0_K5") (pintype "power_in"))
      (node (ref "U1") (pin "L14") (pinfunction "VDDIO_1_L14") (pintype "power_in"))
      (node (ref "U1") (pin "M5") (pinfunction "VDDIO_0_M5") (pintype "power_in"))
      (node (ref "U1") (pin "N10") (pinfunction "VDDIO_0_N10") (pintype "power_in"))
      (node (ref "U1") (pin "N12") (pinfunction "VDDIO_2_N12") (pintype "power_in"))
      (node (ref "U1") (pin "N16") (pinfunction "USB1_VDD3V3_N16") (pintype "power_in"))
      (node (ref "U1") (pin "N6") (pinfunction "VDDIO_0_N6") (pintype "power_in"))
      (node (ref "U1") (pin "N8") (pinfunction "VDDIO_0_N8") (pintype "power_in"))
      (node (ref "U1") (pin "P11") (pinfunction "VDDIO_2_P11") (pintype "power_in"))
      (node (ref "U1") (pin "P12") (pinfunction "VDDIO_2_P12") (pintype "power_in"))
      (node (ref "U6") (pin "B4") (pinfunction "VDD_B4") (pintype "power_in"))
      (node (ref "U6") (pin "D1") (pinfunction "VDDQ_D1") (pintype "power_in"))
      (node (ref "U6") (pin "E4") (pinfunction "VDDQ_E4") (pintype "power_in"))
    )
    (net (code "4") (name "+5vUSB") (class "Default")
      (node (ref "D2") (pin "1") (pinfunction "A_1") (pintype "passive"))
      (node (ref "T55") (pin "1") (pinfunction "1_1") (pintype "passive"))
      (node (ref "U1") (pin "R16") (pinfunction "USB1_VBUS_R16") (pintype "input"))
      (node (ref "U4") (pin "4") (pinfunction "VCC_4") (pintype "passive"))
    )
    (net (code "5") (name "+VBATT") (class "Default")
      (node (ref "C4") (pin "2") (pinfunction "1_2") (pintype "passive"))
      (node (ref "R6") (pin "2") (pinfunction "2_2") (pintype "passive"))
      (node (ref "T56") (pin "1") (pinfunction "1_1") (pintype "passive"))
      (node (ref "U2") (pin "18") (pinfunction "VBAT_18") (pintype "power_in"))
    )
    (net (code "6") (name "+VBATT_BU") (class "Default")
      (node (ref "C3") (pin "2") (pinfunction "1_2") (pintype "passive"))
      (node (ref "R6") (pin "1") (pinfunction "1_1") (pintype "passive"))
      (node (ref "T53") (pin "1") (pinfunction "1_1") (pintype "passive"))
      (node (ref "U2") (pin "13") (pinfunction "VBAT_BKUP_13") (pintype "power_in"))
    )
    (net (code "7") (name "+VIN") (class "Default")
      (node (ref "D1") (pin "1") (pinfunction "A_1") (pintype "passive"))
      (node (ref "T57") (pin "1") (pinfunction "1_1") (pintype "passive"))
    )
    (net (code "8") (name "+VREF") (class "Default")
      (node (ref "C6") (pin "2") (pinfunction "2_2") (pintype "passive"))
      (node (ref "R21") (pin "2") (pinfunction "2_2") (pintype "passive"))
      (node (ref "T1") (pin "1") (pinfunction "1_1") (pintype "passive"))
      (node (ref "U1") (pin "D2") (pinfunction "VREFP_D2") (pintype "power_in"))
    )
    (net (code "9") (name "/ADC0_1") (class "Default")
      (node (ref "T74") (pin "1") (pinfunction "1_1") (pintype "passive"))
      (node (ref "U1") (pin "E3") (pinfunction "PIO0_12/FC1_SSEL2/SCT0_GPI2/SCT0_OUT2/CTIMER_INP3/SEC_PIO0_12/ADC0_1_E3") (pintype "passive"))
    )
    (net (code "10") (name "/ADC0_3") (class "Default")
      (node (ref "T75") (pin "1") (pinfunction "1_1") (pintype "passive"))
      (node (ref "U1") (pin "A2") (pinfunction "PIO0_26/FC3_SSEL2/SCT0_GPI6/SCT0_OUT6/CTIMER_INP7/SEC_PIO0_26/ADC0_3_A2") (pintype "passive"))
    )
    (net (code "11") (name "/ADC0_4") (class "Default")
      (node (ref "T73") (pin "1") (pinfunction "1_1") (pintype "passive"))
      (node (ref "U1") (pin "B5") (pinfunction "PIO1_8/FC5_SSEL2/SCT0_GPI6/CTIMER_INP12/CTIMER1_MAT2/ADC0_4_B5") (pintype "passive"))
    )
    (net (code "12") (name "/ADC0_8") (class "Default")
      (node (ref "T2") (pin "1") (pinfunction "1_1") (pintype "passive"))
      (node (ref "U1") (pin "E1") (pinfunction "PIO0_6/FC0_SSEL3/SCT0_GPI1/SCT0_OUT1/CTIMER0_MAT0/SEC_PIO0_6/ADC0_8_E1") (pintype "passive"))
    )
    (net (code "13") (name "/ADC0_12") (class "Default")
      (node (ref "T76") (pin "1") (pinfunction "1_1") (pintype "passive"))
      (node (ref "U1") (pin "B1") (pinfunction "PIO1_9/FC5_SSEL3/SCT0_GPI7/UTICK_CAP1/CTIMER1_MAT3/ADC0_12_B1") (pintype "passive"))
    )
    (net (code "14") (name "/DM_MCU") (class "Default")
      (node (ref "T43") (pin "1") (pinfunction "1_1") (pintype "passive"))
      (node (ref "U1") (pin "T17") (pinfunction "USB1_DM_T17") (pintype "bidirectional"))
      (node (ref "U4") (pin "2") (pinfunction "IO1_2") (pintype "passive"))
    )
    (net (code "15") (name "/DP_MCU") (class "Default")
      (node (ref "T45") (pin "1") (pinfunction "1_1") (pintype "passive"))
      (node (ref "U1") (pin "R17") (pinfunction "USB1_DP_R17") (pintype "bidirectional"))
      (node (ref "U4") (pin "3") (pinfunction "IO2_3") (pintype "passive"))
    )
    (net (code "16") (name "/FC0_CLK") (class "Default")
      (node (ref "T5") (pin "1") (pinfunction "1_1") (pintype "passive"))
      (node (ref "U1") (pin "G1") (pinfunction "PIO0_0/FC0_SCK/CTIMER0_MAT0/I2S_BRIDGE_CLK_IN/GPIO_INT_BMAT/SEC_PIO0_0_G1") (pintype "passive"))
    )
    (net (code "17") (name "/FC0_RXD") (class "Default")
      (node (ref "T3") (pin "1") (pinfunction "1_1") (pintype "passive"))
      (node (ref "U1") (pin "G4") (pinfunction "PIO0_2/FC0_RXD_SDA_MOSI_DATA/CTIMER0_MAT2/I2S_BRIDGE_DATA_IN/SEC_PIO0_2_G4") (pintype "passive"))
    )
    (net (code "18") (name "/FC0_SSEL0") (class "Default")
      (node (ref "T6") (pin "1") (pinfunction "1_1") (pintype "passive"))
      (node (ref "U1") (pin "H2") (pinfunction "PIO0_3/FC0_CTS_SDA_SSEL0/CTIMER0_MAT3/FC1_SSEL2/SEC_PIO0_3_H2") (pintype "passive"))
    )
    (net (code "19") (name "/FC0_SSEL1") (class "Default")
      (node (ref "T7") (pin "1") (pinfunction "1_1") (pintype "passive"))
      (node (ref "U1") (pin "J1") (pinfunction "PIO0_4/FC0_RTS_SCL_SSEL1/CTIMER_INP0/FC1_SSEL3/CMP0_OUT/SEC_PIO0_4_J1") (pintype "passive"))
    )
    (net (code "20") (name "/FC0_TXD") (class "Default")
      (node (ref "T4") (pin "1") (pinfunction "1_1") (pintype "passive"))
      (node (ref "U1") (pin "G2") (pinfunction "PIO0_1/FC0_TXD_SCL_MISO_WS/CTIMER0_MAT1/I2S_BRIDGE_WS_IN/SEC_PIO0_1_G2") (pintype "passive"))
    )
    (net (code "21") (name "/FC1_CLK") (class "Default")
      (node (ref "T8") (pin "1") (pinfunction "1_1") (pintype "passive"))
      (node (ref "U1") (pin "J2") (pinfunction "PIO0_7/FC1_SCK/SCT0_GPI4/SCT0_OUT4/CTIMER1_MAT0/I2S_BRIDGE_CLK_OUT/SEC_PIO0_7_J2") (pintype "passive"))
    )
    (net (code "22") (name "/FC1_RXD") (class "Default")
      (node (ref "T10") (pin "1") (pinfunction "1_1") (pintype "passive"))
      (node (ref "U1") (pin "L3") (pinfunction "PIO0_9/FC1_RXD_SDA_MOSI_DATA/SCT0_GPI6/SCT0_OUT6/CTIMER1_MAT2/I2S_BRIDGE_DATA_OUT/SEC_PIO0_9_L3") (pintype "passive"))
    )
    (net (code "23") (name "/FC1_SSEL0") (class "Default")
      (node (ref "T9") (pin "1") (pinfunction "1_1") (pintype "passive"))
      (node (ref "U1") (pin "J3") (pinfunction "PIO0_10/FC1_CTS_SDA_SSEL0/SCT0_GPI7/SCT0_OUT7/CTIMER1_MAT3/FC0_SSEL2/SEC_PIO0_10_J3") (pintype "passive"))
    )
    (net (code "24") (name "/FC1_SSEL1") (class "Default")
      (node (ref "T12") (pin "1") (pinfunction "1_1") (pintype "passive"))
      (node (ref "U1") (pin "L1") (pinfunction "PIO0_11/FC1_RTS_SCL_SSEL1/SCT0_GPI0/SCT0_OUT8/CTIMER_INP2/FC0_SSEL3/SEC_PIO0_11_L1") (pintype "passive"))
    )
    (net (code "25") (name "/FC1_TXD") (class "Default")
      (node (ref "T11") (pin "1") (pinfunction "1_1") (pintype "passive"))
      (node (ref "U1") (pin "K4") (pinfunction "PIO0_8/FC1_TXD_SCL_MISO_WS/SCT0_GPI5/SCT0_OUT5/CTIMER1_MAT1/I2S_BRIDGE_WS_OUT/SEC_PIO0_8_K4") (pintype "passive"))
    )
    (net (code "26") (name "/FC2_CLK") (class "Default")
      (node (ref "T62") (pin "1") (pinfunction "1_1") (pintype "passive"))
      (node (ref "U1") (pin "A3") (pinfunction "PIO0_14/FC2_SCK/SCT0_GPI0/SCT0_OUT0/CTIMER2_MAT0/I2S_BRIDGE_CLK_IN/SEC_PIO0_14_A3") (pintype "passive"))
    )
    (net (code "27") (name "/FC2_SDA") (class "Default")
      (node (ref "T59") (pin "1") (pinfunction "1_1") (pintype "passive"))
      (node (ref "U1") (pin "D6") (pinfunction "PIO0_16/FC2_RXD_SDA_MOSI_DATA/SCT0_GPI2/SCT0_OUT2/CTIMER2_MAT2/I2S_BRIDGE_DATA_IN/SEC_PIO0_16_D6") (pintype "passive"))
    )
    (net (code "28") (name "/FC2_SSEL0") (class "Default")
      (node (ref "T58") (pin "1") (pinfunction "1_1") (pintype "passive"))
      (node (ref "U1") (pin "D7") (pinfunction "PIO0_17/FC2_CTS_SDA_SSEL0/SCT0_GPI3/SCT0_OUT3/CTIMER2_MAT3/FC5_SSEL2/SEC_PIO0_17_D7") (pintype "passive"))
    )
    (net (code "29") (name "/FC2_SSEL1") (class "Default")
      (node (ref "T60") (pin "1") (pinfunction "1_1") (pintype "passive"))
      (node (ref "U1") (pin "B7") (pinfunction "PIO0_18/FC2_RTS_SCL_SSEL1/SCT0_GPI6/SCT0_OUT6/CTIMER_INP4/FC5_SSEL3/SEC_PIO0_18_B7") (pintype "passive"))
    )
    (net (code "30") (name "/FC2_WS") (class "Default")
      (node (ref "T61") (pin "1") (pinfunction "1_1") (pintype "passive"))
      (node (ref "U1") (pin "A5") (pinfunction "PIO0_15/FC2_TXD_SCL_MISO_WS/SCT0_GPI1/SCT0_OUT1/CTIMER2_MAT1/I2S_BRIDGE_WS_IN/SEC_PIO0_15_A5") (pintype "passive"))
    )
    (net (code "31") (name "/FC3_CLK") (class "Default")
      (node (ref "T72") (pin "1") (pinfunction "1_1") (pintype "passive"))
      (node (ref "U1") (pin "C7") (pinfunction "PIO0_21/FC3_SCK/CTIMER3_MAT0/TRACECLK/SEC_PIO0_21_C7") (pintype "passive"))
    )
    (net (code "32") (name "/FC3_SDA") (class "Default")
      (node (ref "T70") (pin "1") (pinfunction "1_1") (pintype "passive"))
      (node (ref "U1") (pin "C9") (pinfunction "PIO0_23/FC3_RXD_SDA_MOSI_DATA/CTIMER3_MAT2/TRACEDATA(1)/SEC_PIO0_23_C9") (pintype "passive"))
    )
    (net (code "33") (name "/FC3_SSEL0") (class "Default")
      (node (ref "T68") (pin "1") (pinfunction "1_1") (pintype "passive"))
      (node (ref "U1") (pin "B9") (pinfunction "PIO0_24/FC3_CTS_SDA_SSEL0/CTIMER3_MAT3/FC2_SSEL2/TRACEDATA(2)/CLKOUT/SEC_PIO0_24_B9") (pintype "passive"))
    )
    (net (code "34") (name "/FC3_SSEL1") (class "Default")
      (node (ref "T69") (pin "1") (pinfunction "1_1") (pintype "passive"))
      (node (ref "U1") (pin "A9") (pinfunction "PIO0_25/FC3_RTS_SCL_SSEL1/FREQME_GPIO_CLK/CTIMER_INP6/FC2_SSEL3/TRACEDATA(3)/CLKIN/SEC_PIO0_25_A9") (pintype "passive"))
    )
    (net (code "35") (name "/FC3_WS") (class "Default")
      (node (ref "T71") (pin "1") (pinfunction "1_1") (pintype "passive"))
      (node (ref "U1") (pin "D8") (pinfunction "PIO0_22/FC3_TXD_SCL_MISO_WS/CTIMER3_MAT1/TRACEDATA(0)/SEC_PIO0_22_D8") (pintype "passive"))
    )
    (net (code "36") (name "/FC4_CLK") (class "Default")
      (node (ref "T64") (pin "1") (pinfunction "1_1") (pintype "passive"))
      (node (ref "U1") (pin "D11") (pinfunction "PIO0_28/FC4_SCK/CTIMER4_MAT0/I2S_BRIDGE_CLK_OUT/SEC_PIO0_28_D11") (pintype "passive"))
    )
    (net (code "37") (name "/FC4_SDA") (class "Default")
      (node (ref "T65") (pin "1") (pinfunction "1_1") (pintype "passive"))
      (node (ref "U1") (pin "C11") (pinfunction "PIO0_30/FC4_RXD_SDA_MOSI_DATA/CTIMER4_MAT2/I2S_BRIDGE_DATA_OUT/SEC_PIO0_30_C11") (pintype "passive"))
    )
    (net (code "38") (name "/FC4_SSEL0") (class "Default")
      (node (ref "T66") (pin "1") (pinfunction "1_1") (pintype "passive"))
      (node (ref "U1") (pin "A11") (pinfunction "PIO0_31/FC4_CTS_SDA_SSEL0/SCT0_GPI0/SCT0_OUT6/CTIMER4_MAT3/FC3_SSEL2/SEC_PIO0_31_A11") (pintype "passive"))
    )
    (net (code "39") (name "/FC4_SSEL1") (class "Default")
      (node (ref "T63") (pin "1") (pinfunction "1_1") (pintype "passive"))
      (node (ref "U1") (pin "E17") (pinfunction "PIO1_0/FC4_RTS_SCL_SSEL1/SCT0_GPI1/SCT0_OUT7/CTIMER_INP8/FC3_SSEL3_E17") (pintype "passive"))
    )
    (net (code "40") (name "/FC4_WS") (class "Default")
      (node (ref "T67") (pin "1") (pinfunction "1_1") (pintype "passive"))
      (node (ref "U1") (pin "B10") (pinfunction "PIO0_29/FC4_TXD_SCL_MISO_WS/CTIMER4_MAT1/I2S_BRIDGE_WS_OUT/SEC_PIO0_29_B10") (pintype "passive"))
    )
    (net (code "41") (name "/FC5_RXD") (class "Default")
      (node (ref "T42") (pin "1") (pinfunction "1_1") (pintype "passive"))
      (node (ref "U1") (pin "J16") (pinfunction "PIO1_5/FC5_RXD_SDA_MOSI_DATA_J16") (pintype "passive"))
    )
    (net (code "42") (name "/FC5_SCK") (class "Default")
      (node (ref "T47") (pin "1") (pinfunction "1_1") (pintype "passive"))
      (node (ref "U1") (pin "G16") (pinfunction "PIO1_3/FC5_SCK_G16") (pintype "passive"))
    )
    (net (code "43") (name "/FC5_SSEL0") (class "Default")
      (node (ref "T44") (pin "1") (pinfunction "1_1") (pintype "passive"))
      (node (ref "U1") (pin "J17") (pinfunction "PIO1_6/FC5_CTS_SDA_SSEL0/SCT0_GPI4/SCT0_OUT4/FC4_SSEL2_J17") (pintype "passive"))
    )
    (net (code "44") (name "/FC5_TXD") (class "Default")
      (node (ref "T46") (pin "1") (pinfunction "1_1") (pintype "passive"))
      (node (ref "U1") (pin "G17") (pinfunction "PIO1_4/FC5_TXD_SCL_MISO_WS_G17") (pintype "passive"))
    )
    (net (code "45") (name "/FLEXSPI0A_D0") (class "Default")
      (node (ref "U1") (pin "T5") (pinfunction "PIO1_20/FLEXSPI0A_DATA0/SCT0_GPI1/CTIMER4_MAT1_T5") (pintype "passive"))
      (node (ref "U6") (pin "D3") (pinfunction "ADQ0_D3") (pintype "bidirectional"))
    )
    (net (code "46") (name "/FLEXSPI0A_D1") (class "Default")
      (node (ref "U1") (pin "U5") (pinfunction "PIO1_21/FLEXSPI0A_DATA1/SCT0_OUT1/CTIMER4_MAT2_U5") (pintype "passive"))
      (node (ref "U6") (pin "D2") (pinfunction "ADQ1_D2") (pintype "bidirectional"))
    )
    (net (code "47") (name "/FLEXSPI0A_D2") (class "Default")
      (node (ref "U1") (pin "P6") (pinfunction "PIO1_22/FLEXSPI0A_DATA2/SCT0_GPI2/CTIMER4_MAT3_P6") (pintype "passive"))
      (node (ref "U6") (pin "C4") (pinfunction "ADQ2_C4") (pintype "bidirectional"))
    )
    (net (code "48") (name "/FLEXSPI0A_D3") (class "Default")
      (node (ref "U1") (pin "P7") (pinfunction "PIO1_23/FLEXSPI0A_DATA3/SCT0_OUT2/CTIMER_INP8_P7") (pintype "passive"))
      (node (ref "U6") (pin "D4") (pinfunction "ADQ3_D4") (pintype "bidirectional"))
    )
    (net (code "49") (name "/FLEXSPI0A_D4") (class "Default")
      (node (ref "U1") (pin "T7") (pinfunction "PIO1_24/FLEXSPI0A_DATA4/SCT0_GPI3_T7") (pintype "passive"))
      (node (ref "U6") (pin "D5") (pinfunction "ADQ4_D5") (pintype "bidirectional"))
    )
    (net (code "50") (name "/FLEXSPI0A_D5") (class "Default")
      (node (ref "U1") (pin "U7") (pinfunction "PIO1_25/FLEXSPI0A_DATA5/SCT0_OUT3_U7") (pintype "passive"))
      (node (ref "U6") (pin "E3") (pinfunction "ADQ5_E3") (pintype "bidirectional"))
    )
    (net (code "51") (name "/FLEXSPI0A_D6") (class "Default")
      (node (ref "U1") (pin "R7") (pinfunction "PIO1_26/FLEXSPI0A_DATA6/SCT0_GPI4_R7") (pintype "passive"))
      (node (ref "U6") (pin "E2") (pinfunction "ADQ6_E2") (pintype "bidirectional"))
    )
    (net (code "52") (name "/FLEXSPI0A_D7") (class "Default")
      (node (ref "U1") (pin "T8") (pinfunction "PIO1_27/FLEXSPI0A_DATA7/SCT0_OUT4_T8") (pintype "passive"))
      (node (ref "U6") (pin "E1") (pinfunction "ADQ7_E1") (pintype "bidirectional"))
    )
    (net (code "53") (name "/FLEXSPI0A_DQS") (class "Default")
      (node (ref "U1") (pin "U9") (pinfunction "PIO1_28/FLEXSPI0A_DQS/SCT0_GPI5_U9") (pintype "passive"))
      (node (ref "U6") (pin "C3") (pinfunction "DQS/DM_C3") (pintype "bidirectional"))
    )
    (net (code "54") (name "/FLEXSPI0A_SCK") (class "Default")
      (node (ref "U1") (pin "T9") (pinfunction "PIO1_18/FLEXSPI0A_SCLK/SCT0_GPI0/CTIMER3_MAT3_T9") (pintype "passive"))
      (node (ref "U6") (pin "B2") (pinfunction "CLK_B2") (pintype "input"))
    )
    (net (code "55") (name "/FLEXSPI0A_SS0_N") (class "Default")
      (node (ref "R9") (pin "1") (pinfunction "1_1") (pintype "passive"))
      (node (ref "U1") (pin "T4") (pinfunction "PIO1_19/FLEXSPI0A_SS0_N/SCT0_OUT0/CTIMER4_MAT0_T4") (pintype "passive"))
      (node (ref "U6") (pin "A3") (pinfunction "~{CE}_A3") (pintype "input"))
    )
    (net (code "56") (name "/FLEXSPI0B_CLK") (class "Default")
      (node (ref "T20") (pin "1") (pinfunction "1_1") (pintype "passive"))
      (node (ref "U1") (pin "U3") (pinfunction "PIO1_29/FLEXSPI0A_SS1_N/SCT0_OUT5/UTICK_CAP2/CTIMER_INP13/FLEXSPI0B_SCLK_U3") (pintype "passive"))
    )
    (net (code "57") (name "/HS_SPI_MISO") (class "Default")
      (node (ref "T14") (pin "1") (pinfunction "1_1") (pintype "passive"))
      (node (ref "U1") (pin "M2") (pinfunction "PIO1_12/HS_SPI_MISO/CTIMER2_MAT1/FLEXSPI0B_DATA1_M2") (pintype "passive"))
    )
    (net (code "58") (name "/HS_SPI_MOSI") (class "Default")
      (node (ref "T15") (pin "1") (pinfunction "1_1") (pintype "passive"))
      (node (ref "U1") (pin "N1") (pinfunction "PIO1_13/HS_SPI_MOSI/CTIMER2_MAT2/FLEXSPI0B_DATA2_N1") (pintype "passive"))
    )
    (net (code "59") (name "/HS_SPI_SCK") (class "Default")
      (node (ref "T13") (pin "1") (pinfunction "1_1") (pintype "passive"))
      (node (ref "U1") (pin "L2") (pinfunction "PIO1_11/HS_SPI_SCK/CTIMER2_MAT0/FLEXSPI0B_DATA0_L2") (pintype "passive"))
    )
    (net (code "60") (name "/HS_SPI_SSEL0") (class "Default")
      (node (ref "T16") (pin "1") (pinfunction "1_1") (pintype "passive"))
      (node (ref "U1") (pin "N2") (pinfunction "PIO1_14/HS_SPI_SSEL0/CTIMER2_MAT3/FLEXSPI0B_DATA3_N2") (pintype "passive"))
    )
    (net (code "61") (name "/I3C0_PUR") (class "Default")
      (node (ref "R16") (pin "1") (pinfunction "1_1") (pintype "passive"))
      (node (ref "U1") (pin "B6") (pinfunction "PIO2_31/I3C0_PUR/SCT0_OUT7/UTICK_CAP3/CTIMER_INP15/SWO/CMP0_B_B6") (pintype "passive"))
    )
    (net (code "62") (name "/I3C0_SCL") (class "Default")
      (node (ref "T41") (pin "1") (pinfunction "1_1") (pintype "passive"))
      (node (ref "U1") (pin "N17") (pinfunction "PIO2_29/I3C0_SCL/SCT0_OUT0/CLKOUT_N17") (pintype "passive"))
    )
    (net (code "63") (name "/I3C0_SDA") (class "Default")
      (node (ref "R16") (pin "2") (pinfunction "2_2") (pintype "passive"))
      (node (ref "T40") (pin "1") (pinfunction "1_1") (pintype "passive"))
      (node (ref "U1") (pin "P16") (pinfunction "PIO2_30/I3C0_SDA/SCT0_OUT3/CLKIN/CMP0_OUT_P16") (pintype "passive"))
    )
    (net (code "64") (name "/ISP0") (class "Default")
      (node (ref "R12") (pin "1") (pinfunction "1_1") (pintype "passive"))
      (node (ref "R15") (pin "2") (pinfunction "2_2") (pintype "passive"))
      (node (ref "T17") (pin "1") (pinfunction "1_1") (pintype "passive"))
      (node (ref "U1") (pin "N3") (pinfunction "PIO1_15/HS_SPI_SSEL1/CTIMER3_MAT0/ISP0_N3") (pintype "passive"))
    )
    (net (code "65") (name "/ISP1") (class "Default")
      (node (ref "R13") (pin "1") (pinfunction "1_1") (pintype "passive"))
      (node (ref "R17") (pin "2") (pinfunction "2_2") (pintype "passive"))
      (node (ref "T18") (pin "1") (pinfunction "1_1") (pintype "passive"))
      (node (ref "U1") (pin "M4") (pinfunction "PIO1_16/HS_SPI_SSEL2/SCT0_OUT8/CTIMER3_MAT1/ISP1_M4") (pintype "passive"))
    )
    (net (code "66") (name "/ISP2") (class "Default")
      (node (ref "R14") (pin "1") (pinfunction "1_1") (pintype "passive"))
      (node (ref "R18") (pin "2") (pinfunction "2_2") (pintype "passive"))
      (node (ref "T19") (pin "1") (pinfunction "1_1") (pintype "passive"))
      (node (ref "U1") (pin "N4") (pinfunction "PIO1_17/HS_SPI_SSEL3/SCT0_OUT9/CTIMER3_MAT2/ISP2_N4") (pintype "passive"))
    )
    (net (code "67") (name "/MCLK") (class "Default")
      (node (ref "T48") (pin "1") (pinfunction "1_1") (pintype "passive"))
      (node (ref "U1") (pin "K16") (pinfunction "PIO1_10/MCLK/FREQME_GPIO_CLK/CTIMER_INP10/CLKOUT_K16") (pintype "passive"))
    )
    (net (code "68") (name "/PDM_CLK01") (class "Default")
      (node (ref "T22") (pin "1") (pinfunction "1_1") (pintype "passive"))
      (node (ref "U1") (pin "R1") (pinfunction "PIO2_16/PDM_CLK01_R1") (pintype "passive"))
    )
    (net (code "69") (name "/PDM_CLK23") (class "Default")
      (node (ref "T24") (pin "1") (pinfunction "1_1") (pintype "passive"))
      (node (ref "U1") (pin "U1") (pinfunction "PIO2_17/PDM_CLK23/FLEXSPI0B_DATA4_U1") (pintype "passive"))
    )
    (net (code "70") (name "/PDM_CLK45") (class "Default")
      (node (ref "T26") (pin "1") (pinfunction "1_1") (pintype "passive"))
      (node (ref "U1") (pin "R2") (pinfunction "PIO2_18/PDM_CLK45/FLEXSPI0B_DATA5_R2") (pintype "passive"))
    )
    (net (code "71") (name "/PDM_CLK67") (class "Default")
      (node (ref "T28") (pin "1") (pinfunction "1_1") (pintype "passive"))
      (node (ref "U1") (pin "T2") (pinfunction "PIO2_19/PDM_CLK67/FLEXSPI0B_SS0_N_T2") (pintype "passive"))
    )
    (net (code "72") (name "/PDM_DATA01") (class "Default")
      (node (ref "T21") (pin "1") (pinfunction "1_1") (pintype "passive"))
      (node (ref "U1") (pin "U2") (pinfunction "PIO2_20/PDM_DATA01_U2") (pintype "passive"))
    )
    (net (code "73") (name "/PDM_DATA23") (class "Default")
      (node (ref "T23") (pin "1") (pinfunction "1_1") (pintype "passive"))
      (node (ref "U1") (pin "R3") (pinfunction "PIO2_21/PDM_DATA23/CTIMER_INP14/FLEXSPI0B_SS1_N_R3") (pintype "passive"))
    )
    (net (code "74") (name "/PDM_DATA45") (class "Default")
      (node (ref "T25") (pin "1") (pinfunction "1_1") (pintype "passive"))
      (node (ref "U1") (pin "P3") (pinfunction "PIO2_22/PDM_DATA45/FLEXSPI0B_DATA6_P3") (pintype "passive"))
    )
    (net (code "75") (name "/PDM_DATA67") (class "Default")
      (node (ref "T27") (pin "1") (pinfunction "1_1") (pintype "passive"))
      (node (ref "U1") (pin "P5") (pinfunction "PIO2_23/PDM_DATA67/FLEXSPI0B_DATA7_P5") (pintype "passive"))
    )
    (net (code "76") (name "/PIO0_19") (class "Default")
      (node (ref "R19") (pin "2") (pinfunction "2_2") (pintype "passive"))
      (node (ref "U1") (pin "A1") (pinfunction "PIO0_19/FC2_SSEL2/SCT0_GPI4/SCT0_OUT4/CTIMER_INP5/UTICK_CAP0/SEC_PIO0_19/ADC0_2_A1") (pintype "passive"))
    )
    (net (code "77") (name "/PIO2_4") (class "Default")
      (node (ref "T37") (pin "1") (pinfunction "1_1") (pintype "passive"))
      (node (ref "U1") (pin "T13") (pinfunction "PIO2_4/SD0_WR_PRT/SCT0_OUT2/SD0_DS_T13") (pintype "passive"))
    )
    (net (code "78") (name "/PIO2_5") (class "Default")
      (node (ref "T38") (pin "1") (pinfunction "1_1") (pintype "passive"))
      (node (ref "U1") (pin "U13") (pinfunction "PIO2_5/SD0_D4/SCT0_OUT3_U13") (pintype "passive"))
    )
    (net (code "79") (name "/PIO2_6") (class "Default")
      (node (ref "T39") (pin "1") (pinfunction "1_1") (pintype "passive"))
      (node (ref "U1") (pin "U15") (pinfunction "PIO2_6/SD0_D5/SCT0_GPI4/CTIMER1_MAT0_U15") (pintype "passive"))
    )
    (net (code "80") (name "/PMIC_INTB") (class "Default")
      (node (ref "R2") (pin "1") (pinfunction "1_1") (pintype "passive"))
      (node (ref "U1") (pin "A15") (pinfunction "~{PMIC_IRQ_N}_A15") (pintype "input"))
      (node (ref "U2") (pin "10") (pinfunction "INTB_10") (pintype "output"))
    )
    (net (code "81") (name "/PMIC_MODE0") (class "Default")
      (node (ref "U1") (pin "C15") (pinfunction "PMIC_MODE0_C15") (pintype "output"))
      (node (ref "U2") (pin "7") (pinfunction "MODESEL0_7") (pintype "input"))
    )
    (net (code "82") (name "/PMIC_MODE1") (class "Default")
      (node (ref "U1") (pin "B16") (pinfunction "PMIC_MODE1_B16") (pintype "output"))
      (node (ref "U2") (pin "8") (pinfunction "MODESEL1_8") (pintype "input"))
    )
    (net (code "83") (name "/PMIC_ON") (class "Default")
      (node (ref "T52") (pin "1") (pinfunction "1_1") (pintype "passive"))
      (node (ref "U2") (pin "4") (pinfunction "ON_4") (pintype "input"))
    )
    (net (code "84") (name "/PMIC_RESETN") (class "Default")
      (node (ref "R5") (pin "1") (pinfunction "1_1") (pintype "passive"))
      (node (ref "U1") (pin "B15") (pinfunction "~{RESETN}_B15") (pintype "input"))
      (node (ref "U2") (pin "11") (pinfunction "SYSRSTN_11") (pintype "output"))
      (node (ref "U3") (pin "4") (pinfunction "Y_4") (pintype "passive"))
    )
    (net (code "85") (name "/PMIC_SCL") (class "Default")
      (node (ref "R3") (pin "1") (pinfunction "1_1") (pintype "passive"))
      (node (ref "U1") (pin "E16") (pinfunction "PMIC_I2C_SCL_E16") (pintype "output"))
      (node (ref "U2") (pin "5") (pinfunction "SCL_5") (pintype "input"))
    )
    (net (code "86") (name "/PMIC_SDA") (class "Default")
      (node (ref "R4") (pin "1") (pinfunction "1_1") (pintype "passive"))
      (node (ref "U1") (pin "F16") (pinfunction "PMIC_I2C_SDA_F16") (pintype "bidirectional"))
      (node (ref "U2") (pin "6") (pinfunction "SDA_6") (pintype "bidirectional"))
    )
    (net (code "87") (name "/RED_LED") (class "Default")
      (node (ref "R20") (pin "2") (pinfunction "2_2") (pintype "passive"))
      (node (ref "U1") (pin "B3") (pinfunction "PIO0_27/FC3_SSEL3/SCT0_GPI7/SCT0_OUT7/CTIMER0_MAT3/SEC_PIO0_27/ADC0_11_B3") (pintype "passive"))
    )
    (net (code "88") (name "/RST_3V3") (class "Default")
      (node (ref "J1") (pin "3") (pinfunction "RST_3") (pintype "passive"))
      (node (ref "J2") (pin "10") (pinfunction "~{RST}_10") (pintype "passive"))
      (node (ref "R11") (pin "1") (pinfunction "1_1") (pintype "passive"))
      (node (ref "R8") (pin "1") (pinfunction "1_1") (pintype "passive"))
      (node (ref "T49") (pin "1") (pinfunction "1_1") (pintype "passive"))
      (node (ref "U3") (pin "2") (pinfunction "A_2") (pintype "passive"))
    )
    (net (code "89") (name "/SD_CLK") (class "Default")
      (node (ref "T34") (pin "1") (pinfunction "1_1") (pintype "passive"))
      (node (ref "U1") (pin "P10") (pinfunction "PIO1_30/SD0_CLK/SCT0_GPI0_P10") (pintype "passive"))
    )
    (net (code "90") (name "/SD_CMD") (class "Default")
      (node (ref "T29") (pin "1") (pinfunction "1_1") (pintype "passive"))
      (node (ref "U1") (pin "R9") (pinfunction "PIO1_31/SD0_CMD/SCT0_GPI1_R9") (pintype "passive"))
    )
    (net (code "91") (name "/SD_D0") (class "Default")
      (node (ref "T30") (pin "1") (pinfunction "1_1") (pintype "passive"))
      (node (ref "U1") (pin "R11") (pinfunction "PIO2_0/SD0_D0/SCT0_GPI2_R11") (pintype "passive"))
    )
    (net (code "92") (name "/SD_D1") (class "Default")
      (node (ref "T31") (pin "1") (pinfunction "1_1") (pintype "passive"))
      (node (ref "U1") (pin "T11") (pinfunction "PIO2_1/SD0_D1/SCT0_GPI3_T11") (pintype "passive"))
    )
    (net (code "93") (name "/SD_D2") (class "Default")
      (node (ref "T32") (pin "1") (pinfunction "1_1") (pintype "passive"))
      (node (ref "U1") (pin "U11") (pinfunction "PIO2_2/SD0_D2/SCT0_OUT0_U11") (pintype "passive"))
    )
    (net (code "94") (name "/SD_D3") (class "Default")
      (node (ref "T33") (pin "1") (pinfunction "1_1") (pintype "passive"))
      (node (ref "U1") (pin "T12") (pinfunction "PIO2_3/SD0_D3/SCT0_OUT1_T12") (pintype "passive"))
    )
    (net (code "95") (name "/SD_DETECT_N") (class "Default")
      (node (ref "T36") (pin "1") (pinfunction "1_1") (pintype "passive"))
      (node (ref "U1") (pin "R13") (pinfunction "PIO2_9/SD0_CARD_DET_N/SCT0_OUT5/CTIMER1_MAT3_R13") (pintype "passive"))
    )
    (net (code "96") (name "/SD_RESET_N") (class "Default")
      (node (ref "T35") (pin "1") (pinfunction "1_1") (pintype "passive"))
      (node (ref "U1") (pin "T15") (pinfunction "PIO2_10/SD0_RESET_N/SCT0_GPI6/CTIMER2_MAT0_T15") (pintype "passive"))
    )
    (net (code "97") (name "/SWCLK") (class "Default")
      (node (ref "J1") (pin "4") (pinfunction "SWDCLK_4") (pintype "passive"))
      (node (ref "J2") (pin "4") (pinfunction "SWDCLK/TCK_4") (pintype "passive"))
      (node (ref "U1") (pin "L17") (pinfunction "PIO2_25/SWCLK_L17") (pintype "passive"))
    )
    (net (code "98") (name "/SWIO") (class "Default")
      (node (ref "J1") (pin "2") (pinfunction "SWDIO_2") (pintype "passive"))
      (node (ref "J2") (pin "2") (pinfunction "SWDIO/TMS_2") (pintype "passive"))
      (node (ref "U1") (pin "L15") (pinfunction "PIO2_26/SWDIO_L15") (pintype "passive"))
    )
    (net (code "99") (name "/SWO") (class "Default")
      (node (ref "J1") (pin "6") (pinfunction "SWO_6") (pintype "passive"))
      (node (ref "J2") (pin "6") (pinfunction "SWO/TDO_6") (pintype "passive"))
      (node (ref "U1") (pin "L16") (pinfunction "PIO2_24/SWO/GPIO_INT_BMAT_L16") (pintype "passive"))
    )
    (net (code "100") (name "/TEMP_SENSE") (class "Default")
      (node (ref "T51") (pin "1") (pinfunction "1_1") (pintype "passive"))
      (node (ref "U2") (pin "14") (pinfunction "TS_14") (pintype "input"))
    )
    (net (code "101") (name "GND") (class "Default")
      (node (ref "C1") (pin "1") (pinfunction "1_1") (pintype "passive"))
      (node (ref "C10") (pin "1") (pinfunction "1_1") (pintype "passive"))
      (node (ref "C11") (pin "1") (pinfunction "1_1") (pintype "passive"))
      (node (ref "C12") (pin "1") (pinfunction "1_1") (pintype "passive"))
      (node (ref "C13") (pin "1") (pinfunction "1_1") (pintype "passive"))
      (node (ref "C14") (pin "1") (pinfunction "1_1") (pintype "passive"))
      (node (ref "C15") (pin "1") (pinfunction "1_1") (pintype "passive"))
      (node (ref "C16") (pin "1") (pinfunction "1_1") (pintype "passive"))
      (node (ref "C17") (pin "1") (pinfunction "1_1") (pintype "passive"))
      (node (ref "C18") (pin "1") (pinfunction "1_1") (pintype "passive"))
      (node (ref "C19") (pin "1") (pinfunction "1_1") (pintype "passive"))
      (node (ref "C2") (pin "2") (pinfunction "1_2") (pintype "passive"))
      (node (ref "C20") (pin "1") (pinfunction "1_1") (pintype "passive"))
      (node (ref "C21") (pin "1") (pinfunction "1_1") (pintype "passive"))
      (node (ref "C22") (pin "1") (pinfunction "1_1") (pintype "passive"))
      (node (ref "C23") (pin "1") (pinfunction "1_1") (pintype "passive"))
      (node (ref "C24") (pin "1") (pinfunction "1_1") (pintype "passive"))
      (node (ref "C25") (pin "1") (pinfunction "1_1") (pintype "passive"))
      (node (ref "C26") (pin "1") (pinfunction "1_1") (pintype "passive"))
      (node (ref "C27") (pin "1") (pinfunction "1_1") (pintype "passive"))
      (node (ref "C28") (pin "1") (pinfunction "1_1") (pintype "passive"))
      (node (ref "C29") (pin "1") (pinfunction "1_1") (pintype "passive"))
      (node (ref "C3") (pin "1") (pinfunction "1_1") (pintype "passive"))
      (node (ref "C30") (pin "1") (pinfunction "1_1") (pintype "passive"))
      (node (ref "C31") (pin "1") (pinfunction "1_1") (pintype "passive"))
      (node (ref "C32") (pin "1") (pinfunction "1_1") (pintype "passive"))
      (node (ref "C33") (pin "1") (pinfunction "1_1") (pintype "passive"))
      (node (ref "C34") (pin "1") (pinfunction "1_1") (pintype "passive"))
      (node (ref "C35") (pin "1") (pinfunction "1_1") (pintype "passive"))
      (node (ref "C36") (pin "1") (pinfunction "1_1") (pintype "passive"))
      (node (ref "C37") (pin "1") (pinfunction "1_1") (pintype "passive"))
      (node (ref "C38") (pin "1") (pinfunction "1_1") (pintype "passive"))
      (node (ref "C39") (pin "1") (pinfunction "1_1") (pintype "passive"))
      (node (ref "C4") (pin "1") (pinfunction "1_1") (pintype "passive"))
      (node (ref "C40") (pin "1") (pinfunction "1_1") (pintype "passive"))
      (node (ref "C41") (pin "1") (pinfunction "1_1") (pintype "passive"))
      (node (ref "C42") (pin "2") (pinfunction "1_2") (pintype "passive"))
      (node (ref "C43") (pin "2") (pinfunction "1_2") (pintype "passive"))
      (node (ref "C44") (pin "2") (pinfunction "1_2") (pintype "passive"))
      (node (ref "C45") (pin "2") (pinfunction "1_2") (pintype "passive"))
      (node (ref "C5") (pin "2") (pinfunction "1_2") (pintype "passive"))
      (node (ref "C6") (pin "1") (pinfunction "1_1") (pintype "passive"))
      (node (ref "C7") (pin "1") (pinfunction "1_1") (pintype "passive"))
      (node (ref "C8") (pin "2") (pinfunction "1_2") (pintype "passive"))
      (node (ref "C9") (pin "1") (pinfunction "1_1") (pintype "passive"))
      (node (ref "D3") (pin "C") (pinfunction "C_C") (pintype "passive"))
      (node (ref "D4") (pin "C") (pinfunction "C_C") (pintype "passive"))
      (node (ref "J1") (pin "5") (pinfunction "GND_5") (pintype "passive"))
      (node (ref "J2") (pin "3") (pinfunction "GND_3") (pintype "passive"))
      (node (ref "J2") (pin "5") (pinfunction "GND_5") (pintype "passive"))
      (node (ref "J2") (pin "9") (pinfunction "GND_DETECT_9") (pintype "passive"))
      (node (ref "R1") (pin "1") (pinfunction "1_1") (pintype "passive"))
      (node (ref "R15") (pin "1") (pinfunction "1_1") (pintype "passive"))
      (node (ref "R17") (pin "1") (pinfunction "1_1") (pintype "passive"))
      (node (ref "R18") (pin "1") (pinfunction "1_1") (pintype "passive"))
      (node (ref "T54") (pin "1") (pinfunction "1_1") (pintype "passive"))
      (node (ref "U1") (pin "C2") (pinfunction "VREFN_C2") (pintype "power_in"))
      (node (ref "U1") (pin "C3") (pinfunction "VSSA_C3") (pintype "power_in"))
      (node (ref "U1") (pin "D12") (pinfunction "VSSA_D12") (pintype "power_in"))
      (node (ref "U1") (pin "D15") (pinfunction "VSS_D15") (pintype "power_in"))
      (node (ref "U1") (pin "D5") (pinfunction "VSS_D5") (pintype "power_in"))
      (node (ref "U1") (pin "E12") (pinfunction "VSS_E12") (pintype "power_in"))
      (node (ref "U1") (pin "E14") (pinfunction "VSS_E14") (pintype "power_in"))
      (node (ref "U1") (pin "F11") (pinfunction "VSS_F11") (pintype "power_in"))
      (node (ref "U1") (pin "F7") (pinfunction "VSS_F7") (pintype "power_in"))
      (node (ref "U1") (pin "G12") (pinfunction "VSS_G12") (pintype "power_in"))
      (node (ref "U1") (pin "G6") (pinfunction "VSS_G6") (pintype "power_in"))
      (node (ref "U1") (pin "H10") (pinfunction "VSS_H10") (pintype "power_in"))
      (node (ref "U1") (pin "H8") (pinfunction "VSS_H8") (pintype "power_in"))
      (node (ref "U1") (pin "H9") (pinfunction "VSS_H9") (pintype "power_in"))
      (node (ref "U1") (pin "J10") (pinfunction "VSS_J10") (pintype "power_in"))
      (node (ref "U1") (pin "J8") (pinfunction "VSS_J8") (pintype "power_in"))
      (node (ref "U1") (pin "K10") (pinfunction "VSS_K10") (pintype "power_in"))
      (node (ref "U1") (pin "K8") (pinfunction "VSS_K8") (pintype "power_in"))
      (node (ref "U1") (pin "K9") (pinfunction "VSS_K9") (pintype "power_in"))
      (node (ref "U1") (pin "L12") (pinfunction "VSS_L12") (pintype "power_in"))
      (node (ref "U1") (pin "L6") (pinfunction "VSS_L6") (pintype "power_in"))
      (node (ref "U1") (pin "M11") (pinfunction "VSS_M11") (pintype "power_in"))
      (node (ref "U1") (pin "M13") (pinfunction "VSS_M13") (pintype "power_in"))
      (node (ref "U1") (pin "M7") (pinfunction "VSS_M7") (pintype "power_in"))
      (node (ref "U1") (pin "N14") (pinfunction "VSS_N14") (pintype "power_in"))
      (node (ref "U1") (pin "P13") (pinfunction "VSS_P13") (pintype "power_in"))
      (node (ref "U2") (pin "21") (pinfunction "AGND2_21") (pintype "power_in"))
      (node (ref "U2") (pin "23") (pinfunction "PGND1_23") (pintype "power_in"))
      (node (ref "U2") (pin "24") (pinfunction "PGND2_24") (pintype "power_in"))
      (node (ref "U2") (pin "25") (pinfunction "EXP_25") (pintype "power_in"))
      (node (ref "U2") (pin "9") (pinfunction "AGND1_9") (pintype "power_in"))
      (node (ref "U3") (pin "3") (pinfunction "GND_3") (pintype "passive"))
      (node (ref "U4") (pin "1") (pinfunction "GND_1") (pintype "passive"))
      (node (ref "U6") (pin "B3") (pinfunction "VSS_B3") (pintype "power_in"))
      (node (ref "U6") (pin "C1") (pinfunction "VSSQ_C1") (pintype "power_in"))
      (node (ref "U6") (pin "E5") (pinfunction "VSSQ_E5") (pintype "power_in"))
    )
    (net (code "102") (name "Net-(D1-K)") (class "Default")
      (node (ref "C1") (pin "2") (pinfunction "1_2") (pintype "passive"))
      (node (ref "D1") (pin "2") (pinfunction "K_2") (pintype "passive"))
      (node (ref "D2") (pin "2") (pinfunction "K_2") (pintype "passive"))
      (node (ref "U2") (pin "16") (pinfunction "VIN_16") (pintype "power_in"))
    )
    (net (code "103") (name "Net-(D3-PadA)") (class "Default")
      (node (ref "D3") (pin "A") (pinfunction "A_A") (pintype "passive"))
      (node (ref "R19") (pin "1") (pinfunction "1_1") (pintype "passive"))
    )
    (net (code "104") (name "Net-(D4-PadA)") (class "Default")
      (node (ref "D4") (pin "A") (pinfunction "A_A") (pintype "passive"))
      (node (ref "R20") (pin "1") (pinfunction "1_1") (pintype "passive"))
    )
    (net (code "105") (name "Net-(U1C-LDO_ENABLE)") (class "Default")
      (node (ref "R1") (pin "2") (pinfunction "2_2") (pintype "passive"))
      (node (ref "U1") (pin "A16") (pinfunction "LDO_ENABLE_A16") (pintype "input"))
    )
    (net (code "106") (name "Net-(U1H-RTCXIN)") (class "Default")
      (node (ref "C44") (pin "1") (pinfunction "1_1") (pintype "passive"))
      (node (ref "U1") (pin "B17") (pinfunction "RTCXIN_B17") (pintype "input"))
      (node (ref "X1") (pin "2") (pinfunction "out_2") (pintype "passive"))
    )
    (net (code "107") (name "Net-(U1H-RTCXOUT)") (class "Default")
      (node (ref "C45") (pin "1") (pinfunction "1_1") (pintype "passive"))
      (node (ref "U1") (pin "A17") (pinfunction "RTCXOUT_A17") (pintype "output"))
      (node (ref "X1") (pin "1") (pinfunction "inp_1") (pintype "passive"))
    )
    (net (code "108") (name "Net-(U1H-XTALIN)") (class "Default")
      (node (ref "C11") (pin "2") (pinfunction "1_2") (pintype "passive"))
      (node (ref "U1") (pin "B14") (pinfunction "XTALIN_B14") (pintype "input"))
      (node (ref "X2") (pin "2") (pinfunction "OSC2_2") (pintype "passive"))
    )
    (net (code "109") (name "Net-(U1H-XTALOUT)") (class "Default")
      (node (ref "C19") (pin "2") (pinfunction "1_2") (pintype "passive"))
      (node (ref "U1") (pin "B13") (pinfunction "XTALOUT_B13") (pintype "output"))
      (node (ref "X2") (pin "1") (pinfunction "OSC1_1") (pintype "passive"))
    )
    (net (code "110") (name "Net-(U2-ASYS)") (class "Default")
      (node (ref "C2") (pin "1") (pinfunction "1_1") (pintype "passive"))
      (node (ref "C5") (pin "1") (pinfunction "1_1") (pintype "passive"))
      (node (ref "C8") (pin "1") (pinfunction "1_1") (pintype "passive"))
      (node (ref "U2") (pin "17") (pinfunction "ASYS_17") (pintype "power_in"))
      (node (ref "U2") (pin "2") (pinfunction "PSYS2_2") (pintype "power_in"))
      (node (ref "U2") (pin "20") (pinfunction "PSYS1_20") (pintype "power_in"))
    )
    (net (code "111") (name "Net-(U2-LDO2_OUT)") (class "Default")
      (node (ref "R22") (pin "1") (pinfunction "1_1") (pintype "passive"))
      (node (ref "U2") (pin "15") (pinfunction "LDO2_OUT_15") (pintype "power_in"))
    )
    (net (code "112") (name "Net-(U2-LX1)") (class "Default")
      (node (ref "L2") (pin "1") (pinfunction "1_1") (pintype "passive"))
      (node (ref "U2") (pin "22") (pinfunction "LX1_22") (pintype "power_in"))
    )
    (net (code "113") (name "Net-(U2-LX2)") (class "Default")
      (node (ref "L3") (pin "1") (pinfunction "1_1") (pintype "passive"))
      (node (ref "U2") (pin "1") (pinfunction "LX2_1") (pintype "power_in"))
    )
    (net (code "114") (name "Net-(U2-SW1_OUT)") (class "Default")
      (node (ref "C7") (pin "2") (pinfunction "1_2") (pintype "passive"))
      (node (ref "L2") (pin "2") (pinfunction "2_2") (pintype "passive"))
      (node (ref "R7") (pin "1") (pinfunction "1_1") (pintype "passive"))
      (node (ref "U2") (pin "19") (pinfunction "SW1_OUT_19") (pintype "input"))
    )
    (net (code "115") (name "Net-(U2-SW2_OUT)") (class "Default")
      (node (ref "C9") (pin "2") (pinfunction "1_2") (pintype "passive"))
      (node (ref "L3") (pin "2") (pinfunction "2_2") (pintype "passive"))
      (node (ref "R10") (pin "1") (pinfunction "1_1") (pintype "passive"))
      (node (ref "U2") (pin "3") (pinfunction "SW2_OUT_3") (pintype "input"))
    )
    (net (code "116") (name "Net-(U6-RFU)") (class "Default")
      (node (ref "TP1") (pin "1") (pinfunction "1_1") (pintype "passive"))
      (node (ref "U6") (pin "C2") (pinfunction "RFU_C2") (pintype "passive"))
    )
    (net (code "117") (name "Net-(U6-~{RESET})") (class "Default")
      (node (ref "R11") (pin "2") (pinfunction "2_2") (pintype "passive"))
      (node (ref "U6") (pin "A4") (pinfunction "~{RESET}_A4") (pintype "input"))
    )
    (net (code "118") (name "VDD_CORE") (class "Default")
      (node (ref "C26") (pin "2") (pinfunction "2_2") (pintype "passive"))
      (node (ref "C27") (pin "2") (pinfunction "2_2") (pintype "passive"))
      (node (ref "C28") (pin "2") (pinfunction "2_2") (pintype "passive"))
      (node (ref "C29") (pin "2") (pinfunction "2_2") (pintype "passive"))
      (node (ref "C30") (pin "2") (pinfunction "2_2") (pintype "passive"))
      (node (ref "C31") (pin "2") (pinfunction "2_2") (pintype "passive"))
      (node (ref "C32") (pin "2") (pinfunction "2_2") (pintype "passive"))
      (node (ref "C33") (pin "2") (pinfunction "2_2") (pintype "passive"))
      (node (ref "C34") (pin "2") (pinfunction "2_2") (pintype "passive"))
      (node (ref "C35") (pin "2") (pinfunction "2_2") (pintype "passive"))
      (node (ref "R7") (pin "2") (pinfunction "2_2") (pintype "passive"))
      (node (ref "U1") (pin "C5") (pinfunction "VDDCORE_C5") (pintype "power_in"))
      (node (ref "U1") (pin "D9") (pinfunction "VDDCORE_D9") (pintype "power_in"))
      (node (ref "U1") (pin "F14") (pinfunction "VDDCORE_F14") (pintype "power_in"))
      (node (ref "U1") (pin "J14") (pinfunction "VDDCORE_J14") (pintype "power_in"))
      (node (ref "U1") (pin "J4") (pinfunction "VDDCORE_J4") (pintype "power_in"))
      (node (ref "U1") (pin "P9") (pinfunction "VDDCORE_P9") (pintype "power_in"))
      (node (ref "U1") (pin "R14") (pinfunction "VDDCORE_R14") (pintype "power_in"))
      (node (ref "U1") (pin "R5") (pinfunction "VDDCORE_R5") (pintype "power_in"))
    )
    (net (code "119") (name "unconnected-(J2-KEY-Pad7)") (class "Default")
      (node (ref "J2") (pin "7") (pinfunction "KEY_7") (pintype "passive+no_connect"))
    )
    (net (code "120") (name "unconnected-(J2-TDI-Pad8)") (class "Default")
      (node (ref "J2") (pin "8") (pinfunction "TDI_8") (pintype "passive+no_connect"))
    )
    (net (code "121") (name "unconnected-(U1D-PIO0_5{slash}FC0_SSEL2{slash}SCT0_GPI0{slash}SCT0_OUT0{slash}CTIMER_INP1{slash}SEC_PIO0_5{slash}ADC0_0-PadF4)") (class "Default")
      (node (ref "U1") (pin "F4") (pinfunction "PIO0_5/FC0_SSEL2/SCT0_GPI0/SCT0_OUT0/CTIMER_INP1/SEC_PIO0_5/ADC0_0_F4") (pintype "passive+no_connect"))
    )
    (net (code "122") (name "unconnected-(U1D-PIO0_13{slash}FC1_SSEL3{slash}SCT0_GPI3{slash}SCT0_OUT3{slash}CTIMER0_MAT1{slash}SEC_PIO0_13{slash}ADC0_9-PadG3)") (class "Default")
      (node (ref "U1") (pin "G3") (pinfunction "PIO0_13/FC1_SSEL3/SCT0_GPI3/SCT0_OUT3/CTIMER0_MAT1/SEC_PIO0_13/ADC0_9_G3") (pintype "passive+no_connect"))
    )
    (net (code "123") (name "unconnected-(U1D-PIO2_12{slash}SCT0_OUT6{slash}CTIMER2_MAT2-PadT3)") (class "Default")
      (node (ref "U1") (pin "T3") (pinfunction "PIO2_12/SCT0_OUT6/CTIMER2_MAT2_T3") (pintype "passive+no_connect"))
    )
    (net (code "124") (name "unconnected-(U1D-PIO2_13{slash}SCT0_OUT7{slash}CTIMER2_MAT3{slash}CMP0_OUT-PadT1)") (class "Default")
      (node (ref "U1") (pin "T1") (pinfunction "PIO2_13/SCT0_OUT7/CTIMER2_MAT3/CMP0_OUT_T1") (pintype "passive+no_connect"))
    )
    (net (code "125") (name "unconnected-(U1D-PIO2_14{slash}SCT0_OUT8{slash}CTIMER_INP1{slash}CMP0_A-PadC1)") (class "Default")
      (node (ref "U1") (pin "C1") (pinfunction "PIO2_14/SCT0_OUT8/CTIMER_INP1/CMP0_A_C1") (pintype "passive+no_connect"))
    )
    (net (code "126") (name "unconnected-(U1D-PIO2_15{slash}SCT0_OUT9{slash}CLKIN{slash}CMP0_D-PadE2)") (class "Default")
      (node (ref "U1") (pin "E2") (pinfunction "PIO2_15/SCT0_OUT9/CLKIN/CMP0_D_E2") (pintype "passive+no_connect"))
    )
    (net (code "127") (name "unconnected-(U1E-PIO0_20{slash}FC2_SSEL3{slash}SCT0_GPI5{slash}SCT0_OUT5{slash}CTIMER0_MAT2{slash}CTIMER_INP11{slash}SEC_PIO0_20{slash}ADC0_10-PadB2)") (class "Default")
      (node (ref "U1") (pin "B2") (pinfunction "PIO0_20/FC2_SSEL3/SCT0_GPI5/SCT0_OUT5/CTIMER0_MAT2/CTIMER_INP11/SEC_PIO0_20/ADC0_10_B2") (pintype "passive+no_connect"))
    )
    (net (code "128") (name "unconnected-(U1E-PIO1_1{slash}FC4_SSEL2{slash}SCT0_GPI2{slash}SCT0_OUT8{slash}CTIMER1_MAT0-PadG15)") (class "Default")
      (node (ref "U1") (pin "G15") (pinfunction "PIO1_1/FC4_SSEL2/SCT0_GPI2/SCT0_OUT8/CTIMER1_MAT0_G15") (pintype "passive+no_connect"))
    )
    (net (code "129") (name "unconnected-(U1E-PIO1_2{slash}FC4_SSEL3{slash}SCT0_GPI3{slash}SCT0_OUT9{slash}CTIMER1_MAT1{slash}CMP0_C-PadA7)") (class "Default")
      (node (ref "U1") (pin "A7") (pinfunction "PIO1_2/FC4_SSEL3/SCT0_GPI3/SCT0_OUT9/CTIMER1_MAT1/CMP0_C_A7") (pintype "passive+no_connect"))
    )
    (net (code "130") (name "unconnected-(U1E-PIO1_7{slash}FC5_RTS_SCL_SSEL1{slash}SCT0_GPI5{slash}SCT0_OUT5{slash}CTIMER_INP9{slash}FC4_SSEL3-PadJ15)") (class "Default")
      (node (ref "U1") (pin "J15") (pinfunction "PIO1_7/FC5_RTS_SCL_SSEL1/SCT0_GPI5/SCT0_OUT5/CTIMER_INP9/FC4_SSEL3_J15") (pintype "passive+no_connect"))
    )
    (net (code "131") (name "unconnected-(U1E-PIO2_27{slash}USB1_OVERCURRENTN-PadM14)") (class "Default")
      (node (ref "U1") (pin "M14") (pinfunction "PIO2_27/USB1_OVERCURRENTN_M14") (pintype "passive+no_connect"))
    )
    (net (code "132") (name "unconnected-(U1E-PIO2_28{slash}USB1_PORTPWRN-PadN15)") (class "Default")
      (node (ref "U1") (pin "N15") (pinfunction "PIO2_28/USB1_PORTPWRN_N15") (pintype "passive+no_connect"))
    )
    (net (code "133") (name "unconnected-(U1F-PIO2_7{slash}SD0_D6{slash}SCT0_GPI5{slash}CTIMER1_MAT1-PadU16)") (class "Default")
      (node (ref "U1") (pin "U16") (pinfunction "PIO2_7/SD0_D6/SCT0_GPI5/CTIMER1_MAT1_U16") (pintype "passive+no_connect"))
    )
    (net (code "134") (name "unconnected-(U1F-PIO2_8{slash}SD0_D7{slash}SCT0_OUT4{slash}CTIMER1_MAT2-PadU17)") (class "Default")
      (node (ref "U1") (pin "U17") (pinfunction "PIO2_8/SD0_D7/SCT0_OUT4/CTIMER1_MAT2_U17") (pintype "passive+no_connect"))
    )
    (net (code "135") (name "unconnected-(U1F-PIO2_11{slash}SD0_VOLT{slash}SCT0_GPI7{slash}CTIMER2_MAT1-PadT16)") (class "Default")
      (node (ref "U1") (pin "T16") (pinfunction "PIO2_11/SD0_VOLT/SCT0_GPI7/CTIMER2_MAT1_T16") (pintype "passive+no_connect"))
    )
    (net (code "136") (name "unconnected-(U6-NC-PadA2)") (class "Default")
      (node (ref "U6") (pin "A2") (pinfunction "NC_A2") (pintype "passive+no_connect"))
    )
    (net (code "137") (name "unconnected-(U6-NC-PadA5)") (class "Default")
      (node (ref "U6") (pin "A5") (pinfunction "NC_A5") (pintype "passive+no_connect"))
    )
    (net (code "138") (name "unconnected-(U6-NC-PadB1)") (class "Default")
      (node (ref "U6") (pin "B1") (pinfunction "NC_B1") (pintype "passive+no_connect"))
    )
    (net (code "139") (name "unconnected-(U6-NC-PadB5)") (class "Default")
      (node (ref "U6") (pin "B5") (pinfunction "NC_B5") (pintype "passive+no_connect"))
    )
    (net (code "140") (name "unconnected-(U6-NC-PadC5)") (class "Default")
      (node (ref "U6") (pin "C5") (pinfunction "NC_C5") (pintype "passive+no_connect"))
    )
  )
)
